# N-CW7_Main.net
KiCad netlist of a schematic drawn in Altium Designer
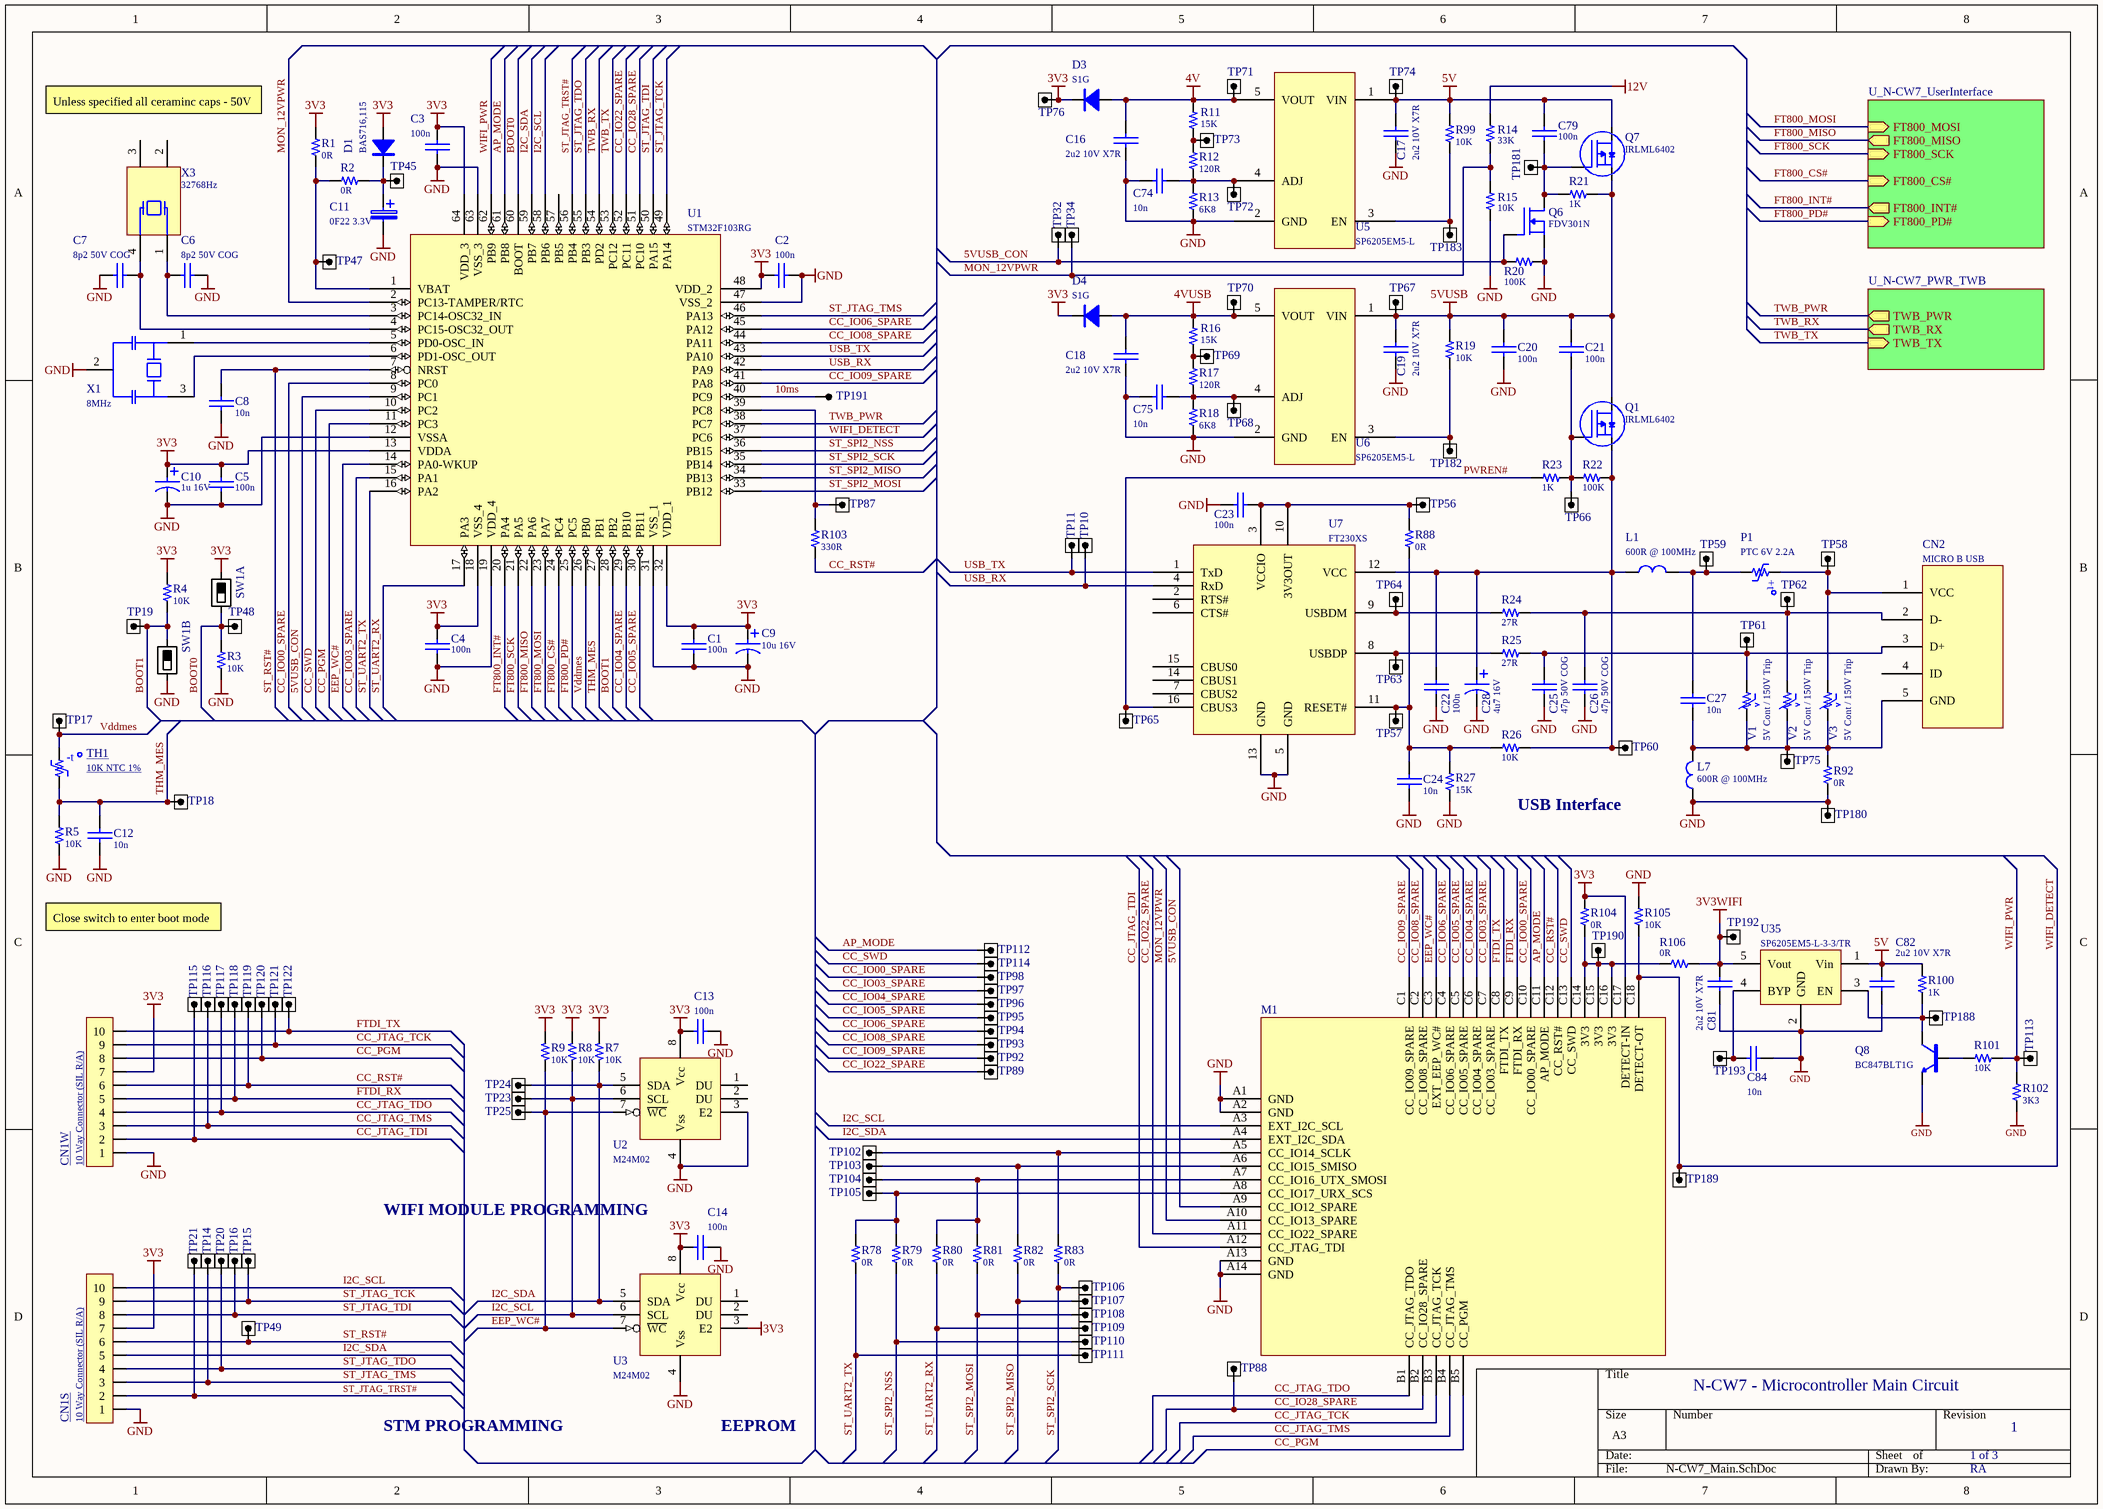
[diagram p0: N-CW7_Main.SchDoc]

(export (version "E")
  (design (tool "Eeschema 10.0.6"))
  (components
    (comp (ref "C1")
      (value "100n")
      (footprint "TDK_0603_T0.80:CAPC1608X08N")
      (description "CAP CER 0.1UF 50V X7R 0603")
      (fields
        (field (name "MANUFACTURER") "TDK")
        (field (name "MANUFACTURER PART NUMBER") "C1608X7R1H104K080AA")
      )
      (libsource (lib "PassiveComponents_Capacitors_Ceramic") (part "TDK_0603_T0.80"))
    )
    (comp (ref "C2")
      (value "100n")
      (footprint "TDK_0603_T0.80:CAPC1608X08N")
      (description "CAP CER 0.1UF 50V X7R 0603")
      (fields
        (field (name "MANUFACTURER") "TDK")
        (field (name "MANUFACTURER PART NUMBER") "C1608X7R1H104K080AA")
      )
      (libsource (lib "PassiveComponents_Capacitors_Ceramic") (part "TDK_0603_T0.80"))
    )
    (comp (ref "C3")
      (value "100n")
      (footprint "TDK_0603_T0.80:CAPC1608X08N")
      (description "CAP CER 0.1UF 50V X7R 0603")
      (fields
        (field (name "MANUFACTURER") "TDK")
        (field (name "MANUFACTURER PART NUMBER") "C1608X7R1H104K080AA")
      )
      (libsource (lib "PassiveComponents_Capacitors_Ceramic") (part "TDK_0603_T0.80"))
    )
    (comp (ref "C4")
      (value "100n")
      (footprint "TDK_0603_T0.80:CAPC1608X08N")
      (description "CAP CER 0.1UF 50V X7R 0603")
      (fields
        (field (name "MANUFACTURER") "TDK")
        (field (name "MANUFACTURER PART NUMBER") "C1608X7R1H104K080AA")
      )
      (libsource (lib "PassiveComponents_Capacitors_Ceramic") (part "TDK_0603_T0.80"))
    )
    (comp (ref "C5")
      (value "100n")
      (footprint "TDK_0603_T0.80:CAPC1608X08N")
      (description "CAP CER 0.1UF 50V X7R 0603")
      (fields
        (field (name "MANUFACTURER") "TDK")
        (field (name "MANUFACTURER PART NUMBER") "C1608X7R1H104K080AA")
      )
      (libsource (lib "PassiveComponents_Capacitors_Ceramic") (part "TDK_0603_T0.80"))
    )
    (comp (ref "C6")
      (value "8p2 50V COG")
      (footprint "KEMET_0603_T0.80:CAPC1608X08N")
      (description "CAP CER 8.2PF 50V C0G/NP0 0603")
      (fields
        (field (name "MANUFACTURER") "KEMET")
        (field (name "MANUFACTURER PART NUMBER") "C0603C829C5GACTU")
      )
      (libsource (lib "PassiveComponents_Capacitors_Ceramic") (part "KEMET_0603_T0.80"))
    )
    (comp (ref "C7")
      (value "8p2 50V COG")
      (footprint "KEMET_0603_T0.80:CAPC1608X08N")
      (description "CAP CER 8.2PF 50V C0G/NP0 0603")
      (fields
        (field (name "MANUFACTURER") "KEMET")
        (field (name "MANUFACTURER PART NUMBER") "C0603C829C5GACTU")
      )
      (libsource (lib "PassiveComponents_Capacitors_Ceramic") (part "KEMET_0603_T0.80"))
    )
    (comp (ref "C8")
      (value "10n")
      (footprint "TDK_0603_T0.80:CAPC1608X08N")
      (description "CAP CER 10000PF 50V X7R 0603")
      (fields
        (field (name "MANUFACTURER") "TDK")
        (field (name "MANUFACTURER PART NUMBER") "C1608X7R1H103K080AA")
      )
      (libsource (lib "PassiveComponents_Capacitors_Ceramic") (part "TDK_0603_T0.80"))
    )
    (comp (ref "C9")
      (value "10u 16V")
      (footprint "KEMET_T494B/3528-21:CAPMP3528X19N")
      (description "CAP TANT 10UF 10% 16V 1411")
      (fields
        (field (name "MANUFACTURER") "KEMET")
        (field (name "MANUFACTURER PART NUMBER") "T494B106K016AT")
      )
      (libsource (lib "PassiveComponents_Capacitors_Tantalum") (part "KEMET_T494B/EIA3528-21"))
    )
    (comp (ref "C10")
      (value "1u 16V")
      (footprint "KEMET_T494A/3216-18:CAPCP3216X16N")
      (description "CAP TANT 1UF 10% 16V 1206")
      (fields
        (field (name "MANUFACTURER") "KEMET")
        (field (name "MANUFACTURER PART NUMBER") "T494A105K016AT")
      )
      (libsource (lib "PassiveComponents_Capacitors_Tantalum") (part "KEMET_T494A/EIA3216-18"))
    )
    (comp (ref "C11")
      (value "0F22 3.3V")
      (footprint "ELNA_RSCSK2243R3D02008U")
      (description "CAP 220MF -20% +80% 3.3V SMD")
      (fields
        (field (name "MANUFACTURER") "Elna")
        (field (name "MANUFACTURER PART NUMBER") "RSCSK2243R3D02008U")
      )
      (libsource (lib "PassiveComponents_Capacitors_Electrolytic") (part "ELNA_RSCSK2243R3D02008U"))
    )
    (comp (ref "C12")
      (value "10n")
      (footprint "TDK_0603_T0.80:CAPC1608X08N")
      (description "CAP CER 10000PF 50V X7R 0603")
      (fields
        (field (name "MANUFACTURER") "TDK")
        (field (name "MANUFACTURER PART NUMBER") "C1608X7R1H103K080AA")
      )
      (libsource (lib "PassiveComponents_Capacitors_Ceramic") (part "TDK_0603_T0.80"))
    )
    (comp (ref "C13")
      (value "100n")
      (footprint "TDK_0603_T0.80:CAPC1608X08N")
      (description "CAP CER 0.1UF 50V X7R 0603")
      (fields
        (field (name "MANUFACTURER") "TDK")
        (field (name "MANUFACTURER PART NUMBER") "C1608X7R1H104K080AA")
      )
      (libsource (lib "PassiveComponents_Capacitors_Ceramic") (part "TDK_0603_T0.80"))
    )
    (comp (ref "C14")
      (value "100n")
      (footprint "TDK_0603_T0.80:CAPC1608X08N")
      (description "CAP CER 0.1UF 50V X7R 0603")
      (fields
        (field (name "MANUFACTURER") "TDK")
        (field (name "MANUFACTURER PART NUMBER") "C1608X7R1H104K080AA")
      )
      (libsource (lib "PassiveComponents_Capacitors_Ceramic") (part "TDK_0603_T0.80"))
    )
    (comp (ref "C16")
      (value "2u2 10V X7R")
      (footprint "TDK_0603_T0.80:CAPC1608X08N")
      (description "CAP CER 2.2UF 10V X7R 0603")
      (fields
        (field (name "MANUFACTURER") "TDK")
        (field (name "MANUFACTURER PART NUMBER") "C1608X7R1A225K080AC")
      )
      (libsource (lib "PassiveComponents_Capacitors_Ceramic") (part "TDK_0603_T0.80"))
    )
    (comp (ref "C17")
      (value "2u2 10V X7R")
      (footprint "TDK_0603_T0.80:CAPC1608X08N")
      (description "CAP CER 2.2UF 10V X7R 0603")
      (fields
        (field (name "MANUFACTURER") "TDK")
        (field (name "MANUFACTURER PART NUMBER") "C1608X7R1A225K080AC")
      )
      (libsource (lib "PassiveComponents_Capacitors_Ceramic") (part "TDK_0603_T0.80"))
    )
    (comp (ref "C18")
      (value "2u2 10V X7R")
      (footprint "TDK_0603_T0.80:CAPC1608X08N")
      (description "CAP CER 2.2UF 10V X7R 0603")
      (fields
        (field (name "MANUFACTURER") "TDK")
        (field (name "MANUFACTURER PART NUMBER") "C1608X7R1A225K080AC")
      )
      (libsource (lib "PassiveComponents_Capacitors_Ceramic") (part "TDK_0603_T0.80"))
    )
    (comp (ref "C19")
      (value "2u2 10V X7R")
      (footprint "TDK_0603_T0.80:CAPC1608X08N")
      (description "CAP CER 2.2UF 10V X7R 0603")
      (fields
        (field (name "MANUFACTURER") "TDK")
        (field (name "MANUFACTURER PART NUMBER") "C1608X7R1A225K080AC")
      )
      (libsource (lib "PassiveComponents_Capacitors_Ceramic") (part "TDK_0603_T0.80"))
    )
    (comp (ref "C20")
      (value "100n")
      (footprint "TDK_0603_T0.80:CAPC1608X08N")
      (description "CAP CER 0.1UF 50V X7R 0603")
      (fields
        (field (name "MANUFACTURER") "TDK")
        (field (name "MANUFACTURER PART NUMBER") "C1608X7R1H104K080AA")
      )
      (libsource (lib "PassiveComponents_Capacitors_Ceramic") (part "TDK_0603_T0.80"))
    )
    (comp (ref "C21")
      (value "100n")
      (footprint "TDK_0603_T0.80:CAPC1608X08N")
      (description "CAP CER 0.1UF 50V X7R 0603")
      (fields
        (field (name "MANUFACTURER") "TDK")
        (field (name "MANUFACTURER PART NUMBER") "C1608X7R1H104K080AA")
      )
      (libsource (lib "PassiveComponents_Capacitors_Ceramic") (part "TDK_0603_T0.80"))
    )
    (comp (ref "C22")
      (value "100n")
      (footprint "TDK_0603_T0.80:CAPC1608X08N")
      (description "CAP CER 0.1UF 50V X7R 0603")
      (fields
        (field (name "MANUFACTURER") "TDK")
        (field (name "MANUFACTURER PART NUMBER") "C1608X7R1H104K080AA")
      )
      (libsource (lib "PassiveComponents_Capacitors_Ceramic") (part "TDK_0603_T0.80"))
    )
    (comp (ref "C23")
      (value "100n")
      (footprint "TDK_0603_T0.80:CAPC1608X08N")
      (description "CAP CER 0.1UF 50V X7R 0603")
      (fields
        (field (name "MANUFACTURER") "TDK")
        (field (name "MANUFACTURER PART NUMBER") "C1608X7R1H104K080AA")
      )
      (libsource (lib "PassiveComponents_Capacitors_Ceramic") (part "TDK_0603_T0.80"))
    )
    (comp (ref "C24")
      (value "10n")
      (footprint "TDK_0603_T0.80:CAPC1608X08N")
      (description "CAP CER 10000PF 50V X7R 0603")
      (fields
        (field (name "MANUFACTURER") "TDK")
        (field (name "MANUFACTURER PART NUMBER") "C1608X7R1H103K080AA")
      )
      (libsource (lib "PassiveComponents_Capacitors_Ceramic") (part "TDK_0603_T0.80"))
    )
    (comp (ref "C25")
      (value "47p 50V COG")
      (footprint "TDK_0603_T0.80:CAPC1608X08N")
      (description "CAP CER 47PF 50V C0G 0603")
      (fields
        (field (name "MANUFACTURER") "TDK")
        (field (name "MANUFACTURER PART NUMBER") "C1608C0G1H470J080AA")
      )
      (libsource (lib "PassiveComponents_Capacitors_Ceramic") (part "TDK_0603_T0.80"))
    )
    (comp (ref "C26")
      (value "47p 50V COG")
      (footprint "TDK_0603_T0.80:CAPC1608X08N")
      (description "CAP CER 47PF 50V C0G 0603")
      (fields
        (field (name "MANUFACTURER") "TDK")
        (field (name "MANUFACTURER PART NUMBER") "C1608C0G1H470J080AA")
      )
      (libsource (lib "PassiveComponents_Capacitors_Ceramic") (part "TDK_0603_T0.80"))
    )
    (comp (ref "C27")
      (value "10n")
      (footprint "TDK_0603_T0.80:CAPC1608X08N")
      (description "CAP CER 10000PF 50V X7R 0603")
      (fields
        (field (name "MANUFACTURER") "TDK")
        (field (name "MANUFACTURER PART NUMBER") "C1608X7R1H103K080AA")
      )
      (libsource (lib "PassiveComponents_Capacitors_Ceramic") (part "TDK_0603_T0.80"))
    )
    (comp (ref "C28")
      (value "4u7 16V")
      (footprint "KEMET_T494A/3216-18:CAPCP3216X16N")
      (description "CAP TANT 4.7UF 10% 16V 1206")
      (fields
        (field (name "MANUFACTURER") "KEMET")
        (field (name "MANUFACTURER PART NUMBER") "T494A475K016AT")
      )
      (libsource (lib "PassiveComponents_Capacitors_Tantalum") (part "KEMET_T494A/EIA3216-18"))
    )
    (comp (ref "C74")
      (value "10n")
      (footprint "TDK_0603_T0.80:CAPC1608X08N")
      (description "CAP CER 10000PF 50V X7R 0603")
      (fields
        (field (name "MANUFACTURER") "TDK")
        (field (name "MANUFACTURER PART NUMBER") "C1608X7R1H103K080AA")
      )
      (libsource (lib "PassiveComponents_Capacitors_Ceramic") (part "TDK_0603_T0.80"))
    )
    (comp (ref "C75")
      (value "10n")
      (footprint "TDK_0603_T0.80:CAPC1608X08N")
      (description "CAP CER 10000PF 50V X7R 0603")
      (fields
        (field (name "MANUFACTURER") "TDK")
        (field (name "MANUFACTURER PART NUMBER") "C1608X7R1H103K080AA")
      )
      (libsource (lib "PassiveComponents_Capacitors_Ceramic") (part "TDK_0603_T0.80"))
    )
    (comp (ref "C79")
      (value "100n")
      (footprint "TDK_0603_T0.80:CAPC1608X08N")
      (description "CAP CER 0.1UF 50V X7R 0603")
      (fields
        (field (name "MANUFACTURER") "TDK")
        (field (name "MANUFACTURER PART NUMBER") "C1608X7R1H104K080AA")
      )
      (libsource (lib "PassiveComponents_Capacitors_Ceramic") (part "TDK_0603_T0.80"))
    )
    (comp (ref "C81")
      (value "2u2 10V X7R")
      (footprint "TDK_0603_T0.80:CAPC1608X08N")
      (description "CAP CER 2.2UF 10V X7R 0603")
      (fields
        (field (name "MANUFACTURER") "TDK")
        (field (name "MANUFACTURER PART NUMBER") "C1608X7R1A225K080AC")
      )
      (libsource (lib "PassiveComponents_Capacitors_Ceramic") (part "TDK_0603_T0.80"))
    )
    (comp (ref "C82")
      (value "2u2 10V X7R")
      (footprint "TDK_0603_T0.80:CAPC1608X08N")
      (description "CAP CER 2.2UF 10V X7R 0603")
      (fields
        (field (name "MANUFACTURER") "TDK")
        (field (name "MANUFACTURER PART NUMBER") "C1608X7R1A225K080AC")
      )
      (libsource (lib "PassiveComponents_Capacitors_Ceramic") (part "TDK_0603_T0.80"))
    )
    (comp (ref "C84")
      (value "10n")
      (footprint "TDK_0603_T0.80:CAPC1608X08N")
      (description "CAP CER 10000PF 50V X7R 0603")
      (fields
        (field (name "MANUFACTURER") "TDK")
        (field (name "MANUFACTURER PART NUMBER") "C1608X7R1H103K080AA")
      )
      (libsource (lib "PassiveComponents_Capacitors_Ceramic") (part "TDK_0603_T0.80"))
    )
    (comp (ref "CN1S")
      (value "10 Way Connector (SIL R/A)")
      (footprint "SULLINS_PPTC101LGBN-RC")
      (description "CONN HDR 10POS 0.1 TIN PCB R/A")
      (fields
        (field (name "MANUFACTURER") "Sullins")
        (field (name "MANUFACTURER PART NUMBER") "PPTC101LGBN-RC")
      )
      (libsource (lib "Connectors") (part "SULLINS_10W_SIL_HDR_RA_2.54MM"))
    )
    (comp (ref "CN1W")
      (value "10 Way Connector (SIL R/A)")
      (footprint "SULLINS_PPTC101LGBN-RC")
      (description "CONN HDR 10POS 0.1 TIN PCB R/A")
      (fields
        (field (name "MANUFACTURER") "Sullins")
        (field (name "MANUFACTURER PART NUMBER") "PPTC101LGBN-RC")
      )
      (libsource (lib "Connectors") (part "SULLINS_10W_SIL_HDR_RA_2.54MM"))
    )
    (comp (ref "CN2")
      (value "MICRO B USB")
      (footprint "MOLEX:47346-1001")
      (description "CONN RCPT USB2.0 MICRO B SMD R/A")
      (fields (field (name "MANUFACTURER") "Molex") (field (name "MANUFACTURER PART NUMBER") "47346-1001"))
      (libsource (lib "Connectors") (part "MOLEX_USB_MICRO_B_SMD_RA"))
    )
    (comp (ref "D1")
      (value "BAS716,115")
      (footprint "NEXPERIA_BAS716,115_SOD523:SODFL160X65-2N")
      (description "DIODE STANDARD 75V 200MA SOD523")
      (fields (field (name "MANUFACTURER") "Nexperia") (field (name "MANUFACTURER PART NUMBER") "BAS716115"))
      (libsource (lib "DiscreteSemiconductors_Diodes_Rectifier") (part "NEXPERIA_BAS716,115_SOD523"))
    )
    (comp (ref "D3")
      (value "S1G")
      (footprint "DIODESINC_S1G_SMA_D0214AC:DIOM4326X24N")
      (description "DIODE GEN PURP 400V 1A SMA")
      (fields (field (name "MANUFACTURER") "Diodes") (field (name "MANUFACTURER PART NUMBER") "S1G-13-F"))
      (libsource (lib "DiscreteSemiconductors_Diodes_Rectifier") (part "DIODESINC_S1G_SMA_D0214AC"))
    )
    (comp (ref "D4")
      (value "S1G")
      (footprint "DIODESINC_S1G_SMA_D0214AC:DIOM4326X24N")
      (description "DIODE GEN PURP 400V 1A SMA")
      (fields (field (name "MANUFACTURER") "Diodes") (field (name "MANUFACTURER PART NUMBER") "S1G-13-F"))
      (libsource (lib "DiscreteSemiconductors_Diodes_Rectifier") (part "DIODESINC_S1G_SMA_D0214AC"))
    )
    (comp (ref "L1")
      (value "600R @ 100MHz")
      (footprint "LAIRD_MI0805K601R-10:INDC2012X09N")
      (description "FERRITE BEAD 600 OHM 0805 1LN")
      (fields
        (field (name "MANUFACTURER") "Laird")
        (field (name "MANUFACTURER PART NUMBER") "MI0805K601R-10")
      )
      (libsource (lib "PassiveComponents_Inductors") (part "LAIRD_MI0805K601R-10"))
    )
    (comp (ref "L7")
      (value "600R @ 100MHz")
      (footprint "LAIRD_MI0805K601R-10:INDC2012X09N")
      (description "FERRITE BEAD 600 OHM 0805 1LN")
      (fields
        (field (name "MANUFACTURER") "Laird")
        (field (name "MANUFACTURER PART NUMBER") "MI0805K601R-10")
      )
      (libsource (lib "PassiveComponents_Inductors") (part "LAIRD_MI0805K601R-10"))
    )
    (comp (ref "M1")
      (value "MB-WIFI-CC3200Rev01")
      (footprint "MB-WIFI-CC3200Rev01")
      (description "Module - Wi-Fi Module (CC3200)")
      (libsource (lib "CustomModules") (part "MB-WIFI-CC3200Rev01"))
    )
    (comp (ref "P1")
      (value "PTC 6V 2.2A")
      (footprint "BOURNS_MF-MSMF110-2:INDC4632X08N")
      (description "PTC RESET FUSE 24V 1.1A 1812")
      (fields
        (field (name "MANUFACTURER") "Bourns")
        (field (name "MANUFACTURER PART NUMBER") "MF-MSMF110/24X-2")
      )
      (libsource (lib "CircuitProtection_Fuses") (part "BOURNS_MF-MSMF110-2"))
    )
    (comp (ref "Q1")
      (value "IRLML6402")
      (footprint "IR_IRLML6402TRPBF_SOT23:SOT95P237X112-3N")
      (description "MOSFET P-CH 20V 3.7A SOT23")
      (fields
        (field (name "MANUFACTURER") "Infineon")
        (field (name "MANUFACTURER PART NUMBER") "IRLML6402TRPBF")
      )
      (libsource (lib "DiscreteSemiconductors_Transistors_JFETs") (part "IR_IRLML6402TRPBF_SOT23"))
    )
    (comp (ref "Q6")
      (value "FDV301N")
      (footprint "ONSEMI_FDV301N_SOT23:SOT95P230X110-3N")
      (description "MOSFET N-CH 25V 220MA SOT23")
      (fields (field (name "MANUFACTURER") "ON Semiconductor / Fairchild"))
      (libsource (lib "DiscreteSemiconductors_Transistors_JFETs") (part "ONSEMI_FDV301N_SOT23"))
    )
    (comp (ref "Q7")
      (value "IRLML6402")
      (footprint "IR_IRLML6402TRPBF_SOT23:SOT95P237X112-3N")
      (description "MOSFET P-CH 20V 3.7A SOT23")
      (fields
        (field (name "MANUFACTURER") "Infineon")
        (field (name "MANUFACTURER PART NUMBER") "IRLML6402TRPBF")
      )
      (libsource (lib "DiscreteSemiconductors_Transistors_JFETs") (part "IR_IRLML6402TRPBF_SOT23"))
    )
    (comp (ref "Q8")
      (value "BC847BLT1G")
      (footprint "ONSEMI_BC847BLT1G_SOT23:SOT95P230X110-3N")
      (description "TRANS NPN 45V 100MA SOT23-3")
      (fields (field (name "MANUFACTURER") "ON Semiconductor"))
      (libsource (lib "DiscreteSemiconductors_Transistors_BJTs") (part "ONSEMI_BC847BLT1G_SOT23"))
    )
    (comp (ref "R1")
      (value "0R")
      (footprint "YAGEO_0603_T0.55:RESC1608X06N")
      (description "RES 0 OHM JUMPER 1/10W 0603")
      (fields
        (field (name "MANUFACTURER") "Yageo")
        (field (name "MANUFACTURER PART NUMBER") "RC0603FR-070RL")
      )
      (libsource (lib "PassiveComponents_Resistors_ChipSMD") (part "YAGEO_0603_T0.55"))
    )
    (comp (ref "R2")
      (value "0R")
      (footprint "YAGEO_0603_T0.55:RESC1608X06N")
      (description "RES 0 OHM JUMPER 1/10W 0603")
      (fields
        (field (name "MANUFACTURER") "Yageo")
        (field (name "MANUFACTURER PART NUMBER") "RC0603FR-070RL")
      )
      (libsource (lib "PassiveComponents_Resistors_ChipSMD") (part "YAGEO_0603_T0.55"))
    )
    (comp (ref "R3")
      (value "10K")
      (footprint "YAGEO_0603_T0.55:RESC1608X06N")
      (description "RES 10K OHM 1% 1/10W 0603")
      (fields
        (field (name "MANUFACTURER") "Yageo")
        (field (name "MANUFACTURER PART NUMBER") "RC0603FR-0710KL")
      )
      (libsource (lib "PassiveComponents_Resistors_ChipSMD") (part "YAGEO_0603_T0.55"))
    )
    (comp (ref "R4")
      (value "10K")
      (footprint "YAGEO_0603_T0.55:RESC1608X06N")
      (description "RES 10K OHM 1% 1/10W 0603")
      (fields
        (field (name "MANUFACTURER") "Yageo")
        (field (name "MANUFACTURER PART NUMBER") "RC0603FR-0710KL")
      )
      (libsource (lib "PassiveComponents_Resistors_ChipSMD") (part "YAGEO_0603_T0.55"))
    )
    (comp (ref "R5")
      (value "10K")
      (footprint "YAGEO_0603_T0.55:RESC1608X06N")
      (description "RES 10K OHM 1% 1/10W 0603")
      (fields
        (field (name "MANUFACTURER") "Yageo")
        (field (name "MANUFACTURER PART NUMBER") "RC0603FR-0710KL")
      )
      (libsource (lib "PassiveComponents_Resistors_ChipSMD") (part "YAGEO_0603_T0.55"))
    )
    (comp (ref "R7")
      (value "10K")
      (footprint "YAGEO_0603_T0.55:RESC1608X06N")
      (description "RES 10K OHM 1% 1/10W 0603")
      (fields
        (field (name "MANUFACTURER") "Yageo")
        (field (name "MANUFACTURER PART NUMBER") "RC0603FR-0710KL")
      )
      (libsource (lib "PassiveComponents_Resistors_ChipSMD") (part "YAGEO_0603_T0.55"))
    )
    (comp (ref "R8")
      (value "10K")
      (footprint "YAGEO_0603_T0.55:RESC1608X06N")
      (description "RES 10K OHM 1% 1/10W 0603")
      (fields
        (field (name "MANUFACTURER") "Yageo")
        (field (name "MANUFACTURER PART NUMBER") "RC0603FR-0710KL")
      )
      (libsource (lib "PassiveComponents_Resistors_ChipSMD") (part "YAGEO_0603_T0.55"))
    )
    (comp (ref "R9")
      (value "10K")
      (footprint "YAGEO_0603_T0.55:RESC1608X06N")
      (description "RES 10K OHM 1% 1/10W 0603")
      (fields
        (field (name "MANUFACTURER") "Yageo")
        (field (name "MANUFACTURER PART NUMBER") "RC0603FR-0710KL")
      )
      (libsource (lib "PassiveComponents_Resistors_ChipSMD") (part "YAGEO_0603_T0.55"))
    )
    (comp (ref "R11")
      (value "15K")
      (footprint "YAGEO_0603_T0.55:RESC1608X06N")
      (description "RES 15K OHM 1% 1/10W 0603")
      (fields
        (field (name "MANUFACTURER") "Yageo")
        (field (name "MANUFACTURER PART NUMBER") "RC0603FR-0715KL")
      )
      (libsource (lib "PassiveComponents_Resistors_ChipSMD") (part "YAGEO_0603_T0.55"))
    )
    (comp (ref "R12")
      (value "120R")
      (footprint "YAGEO_0603_T0.55:RESC1608X06N")
      (description "RES 120 OHM 1% 1/10W 0603")
      (fields
        (field (name "MANUFACTURER") "Yageo")
        (field (name "MANUFACTURER PART NUMBER") "RC0603FR-07120RL")
      )
      (libsource (lib "PassiveComponents_Resistors_ChipSMD") (part "YAGEO_0603_T0.55"))
    )
    (comp (ref "R13")
      (value "6K8")
      (footprint "YAGEO_0603_T0.55:RESC1608X06N")
      (description "RES 6.8K OHM 1% 1/10W 0603")
      (fields
        (field (name "MANUFACTURER") "Yageo")
        (field (name "MANUFACTURER PART NUMBER") "RC0603FR-076K8L")
      )
      (libsource (lib "PassiveComponents_Resistors_ChipSMD") (part "YAGEO_0603_T0.55"))
    )
    (comp (ref "R14")
      (value "33K")
      (footprint "YAGEO_0603_T0.55:RESC1608X06N")
      (description "RES 33K OHM 1% 1/10W 0603")
      (fields
        (field (name "MANUFACTURER") "Yageo")
        (field (name "MANUFACTURER PART NUMBER") "RC0603FR-0733KL")
      )
      (libsource (lib "PassiveComponents_Resistors_ChipSMD") (part "YAGEO_0603_T0.55"))
    )
    (comp (ref "R15")
      (value "10K")
      (footprint "YAGEO_0603_T0.55:RESC1608X06N")
      (description "RES 10K OHM 1% 1/10W 0603")
      (fields
        (field (name "MANUFACTURER") "Yageo")
        (field (name "MANUFACTURER PART NUMBER") "RC0603FR-0710KL")
      )
      (libsource (lib "PassiveComponents_Resistors_ChipSMD") (part "YAGEO_0603_T0.55"))
    )
    (comp (ref "R16")
      (value "15K")
      (footprint "YAGEO_0603_T0.55:RESC1608X06N")
      (description "RES 15K OHM 1% 1/10W 0603")
      (fields
        (field (name "MANUFACTURER") "Yageo")
        (field (name "MANUFACTURER PART NUMBER") "RC0603FR-0715KL")
      )
      (libsource (lib "PassiveComponents_Resistors_ChipSMD") (part "YAGEO_0603_T0.55"))
    )
    (comp (ref "R17")
      (value "120R")
      (footprint "YAGEO_0603_T0.55:RESC1608X06N")
      (description "RES 120 OHM 1% 1/10W 0603")
      (fields
        (field (name "MANUFACTURER") "Yageo")
        (field (name "MANUFACTURER PART NUMBER") "RC0603FR-07120RL")
      )
      (libsource (lib "PassiveComponents_Resistors_ChipSMD") (part "YAGEO_0603_T0.55"))
    )
    (comp (ref "R18")
      (value "6K8")
      (footprint "YAGEO_0603_T0.55:RESC1608X06N")
      (description "RES 6.8K OHM 1% 1/10W 0603")
      (fields
        (field (name "MANUFACTURER") "Yageo")
        (field (name "MANUFACTURER PART NUMBER") "RC0603FR-076K8L")
      )
      (libsource (lib "PassiveComponents_Resistors_ChipSMD") (part "YAGEO_0603_T0.55"))
    )
    (comp (ref "R19")
      (value "10K")
      (footprint "YAGEO_0603_T0.55:RESC1608X06N")
      (description "RES 10K OHM 1% 1/10W 0603")
      (fields
        (field (name "MANUFACTURER") "Yageo")
        (field (name "MANUFACTURER PART NUMBER") "RC0603FR-0710KL")
      )
      (libsource (lib "PassiveComponents_Resistors_ChipSMD") (part "YAGEO_0603_T0.55"))
    )
    (comp (ref "R20")
      (value "100K")
      (footprint "YAGEO_0603_T0.55:RESC1608X06N")
      (description "RES 100K OHM 1% 1/10W 0603")
      (fields
        (field (name "MANUFACTURER") "Yageo")
        (field (name "MANUFACTURER PART NUMBER") "RC0603FR-07100KL")
      )
      (libsource (lib "PassiveComponents_Resistors_ChipSMD") (part "YAGEO_0603_T0.55"))
    )
    (comp (ref "R21")
      (value "1K")
      (footprint "YAGEO_0603_T0.55:RESC1608X06N")
      (description "RES 1K OHM 1% 1/10W 0603")
      (fields
        (field (name "MANUFACTURER") "Yageo")
        (field (name "MANUFACTURER PART NUMBER") "RC0603FR-071KL")
      )
      (libsource (lib "PassiveComponents_Resistors_ChipSMD") (part "YAGEO_0603_T0.55"))
    )
    (comp (ref "R22")
      (value "100K")
      (footprint "YAGEO_0603_T0.55:RESC1608X06N")
      (description "RES 100K OHM 1% 1/10W 0603")
      (fields
        (field (name "MANUFACTURER") "Yageo")
        (field (name "MANUFACTURER PART NUMBER") "RC0603FR-07100KL")
      )
      (libsource (lib "PassiveComponents_Resistors_ChipSMD") (part "YAGEO_0603_T0.55"))
    )
    (comp (ref "R23")
      (value "1K")
      (footprint "YAGEO_0603_T0.55:RESC1608X06N")
      (description "RES 1K OHM 1% 1/10W 0603")
      (fields
        (field (name "MANUFACTURER") "Yageo")
        (field (name "MANUFACTURER PART NUMBER") "RC0603FR-071KL")
      )
      (libsource (lib "PassiveComponents_Resistors_ChipSMD") (part "YAGEO_0603_T0.55"))
    )
    (comp (ref "R24")
      (value "27R")
      (footprint "YAGEO_0603_T0.55:RESC1608X06N")
      (description "RES 27 OHM 1% 1/10W 0603")
      (fields
        (field (name "MANUFACTURER") "Yageo")
        (field (name "MANUFACTURER PART NUMBER") "RC0603FR-0727RL")
      )
      (libsource (lib "PassiveComponents_Resistors_ChipSMD") (part "YAGEO_0603_T0.55"))
    )
    (comp (ref "R25")
      (value "27R")
      (footprint "YAGEO_0603_T0.55:RESC1608X06N")
      (description "RES 27 OHM 1% 1/10W 0603")
      (fields
        (field (name "MANUFACTURER") "Yageo")
        (field (name "MANUFACTURER PART NUMBER") "RC0603FR-0727RL")
      )
      (libsource (lib "PassiveComponents_Resistors_ChipSMD") (part "YAGEO_0603_T0.55"))
    )
    (comp (ref "R26")
      (value "10K")
      (footprint "YAGEO_0603_T0.55:RESC1608X06N")
      (description "RES 10K OHM 1% 1/10W 0603")
      (fields
        (field (name "MANUFACTURER") "Yageo")
        (field (name "MANUFACTURER PART NUMBER") "RC0603FR-0710KL")
      )
      (libsource (lib "PassiveComponents_Resistors_ChipSMD") (part "YAGEO_0603_T0.55"))
    )
    (comp (ref "R27")
      (value "15K")
      (footprint "YAGEO_0603_T0.55:RESC1608X06N")
      (description "RES 15K OHM 1% 1/10W 0603")
      (fields
        (field (name "MANUFACTURER") "Yageo")
        (field (name "MANUFACTURER PART NUMBER") "RC0603FR-0715KL")
      )
      (libsource (lib "PassiveComponents_Resistors_ChipSMD") (part "YAGEO_0603_T0.55"))
    )
    (comp (ref "R78")
      (value "0R")
      (footprint "YAGEO_0603_T0.55:RESC1608X06N")
      (description "RES 0 OHM JUMPER 1/10W 0603")
      (fields
        (field (name "MANUFACTURER") "Yageo")
        (field (name "MANUFACTURER PART NUMBER") "RC0603FR-070RL")
      )
      (libsource (lib "PassiveComponents_Resistors_ChipSMD") (part "YAGEO_0603_T0.55"))
    )
    (comp (ref "R79")
      (value "0R")
      (footprint "YAGEO_0603_T0.55:RESC1608X06N")
      (description "RES 0 OHM JUMPER 1/10W 0603")
      (fields
        (field (name "MANUFACTURER") "Yageo")
        (field (name "MANUFACTURER PART NUMBER") "RC0603FR-070RL")
      )
      (libsource (lib "PassiveComponents_Resistors_ChipSMD") (part "YAGEO_0603_T0.55"))
    )
    (comp (ref "R80")
      (value "0R")
      (footprint "YAGEO_0603_T0.55:RESC1608X06N")
      (description "RES 0 OHM JUMPER 1/10W 0603")
      (fields
        (field (name "MANUFACTURER") "Yageo")
        (field (name "MANUFACTURER PART NUMBER") "RC0603FR-070RL")
      )
      (libsource (lib "PassiveComponents_Resistors_ChipSMD") (part "YAGEO_0603_T0.55"))
    )
    (comp (ref "R81")
      (value "0R")
      (footprint "YAGEO_0603_T0.55:RESC1608X06N")
      (description "RES 0 OHM JUMPER 1/10W 0603")
      (fields
        (field (name "MANUFACTURER") "Yageo")
        (field (name "MANUFACTURER PART NUMBER") "RC0603FR-070RL")
      )
      (libsource (lib "PassiveComponents_Resistors_ChipSMD") (part "YAGEO_0603_T0.55"))
    )
    (comp (ref "R82")
      (value "0R")
      (footprint "YAGEO_0603_T0.55:RESC1608X06N")
      (description "RES 0 OHM JUMPER 1/10W 0603")
      (fields
        (field (name "MANUFACTURER") "Yageo")
        (field (name "MANUFACTURER PART NUMBER") "RC0603FR-070RL")
      )
      (libsource (lib "PassiveComponents_Resistors_ChipSMD") (part "YAGEO_0603_T0.55"))
    )
    (comp (ref "R83")
      (value "0R")
      (footprint "YAGEO_0603_T0.55:RESC1608X06N")
      (description "RES 0 OHM JUMPER 1/10W 0603")
      (fields
        (field (name "MANUFACTURER") "Yageo")
        (field (name "MANUFACTURER PART NUMBER") "RC0603FR-070RL")
      )
      (libsource (lib "PassiveComponents_Resistors_ChipSMD") (part "YAGEO_0603_T0.55"))
    )
    (comp (ref "R88")
      (value "0R")
      (footprint "YAGEO_0603_T0.55:RESC1608X06N")
      (description "RES 0 OHM JUMPER 1/10W 0603")
      (fields
        (field (name "MANUFACTURER") "Yageo")
        (field (name "MANUFACTURER PART NUMBER") "RC0603FR-070RL")
      )
      (libsource (lib "PassiveComponents_Resistors_ChipSMD") (part "YAGEO_0603_T0.55"))
    )
    (comp (ref "R92")
      (value "0R")
      (footprint "YAGEO_0603_T0.55:RESC1608X06N")
      (description "RES 0 OHM JUMPER 1/10W 0603")
      (fields
        (field (name "MANUFACTURER") "Yageo")
        (field (name "MANUFACTURER PART NUMBER") "RC0603FR-070RL")
      )
      (libsource (lib "PassiveComponents_Resistors_ChipSMD") (part "YAGEO_0603_T0.55"))
    )
    (comp (ref "R99")
      (value "10K")
      (footprint "YAGEO_0603_T0.55:RESC1608X06N")
      (description "RES 10K OHM 1% 1/10W 0603")
      (fields
        (field (name "MANUFACTURER") "Yageo")
        (field (name "MANUFACTURER PART NUMBER") "RC0603FR-0710KL")
      )
      (libsource (lib "PassiveComponents_Resistors_ChipSMD") (part "YAGEO_0603_T0.55"))
    )
    (comp (ref "R100")
      (value "1K")
      (footprint "YAGEO_0603_T0.55:RESC1608X06N")
      (description "RES 1K OHM 1% 1/10W 0603")
      (fields
        (field (name "MANUFACTURER") "Yageo")
        (field (name "MANUFACTURER PART NUMBER") "RC0603FR-071KL")
      )
      (libsource (lib "PassiveComponents_Resistors_ChipSMD") (part "YAGEO_0603_T0.55"))
    )
    (comp (ref "R101")
      (value "10K")
      (footprint "YAGEO_0603_T0.55:RESC1608X06N")
      (description "RES 10K OHM 1% 1/10W 0603")
      (fields
        (field (name "MANUFACTURER") "Yageo")
        (field (name "MANUFACTURER PART NUMBER") "RC0603FR-0710KL")
      )
      (libsource (lib "PassiveComponents_Resistors_ChipSMD") (part "YAGEO_0603_T0.55"))
    )
    (comp (ref "R102")
      (value "3K3")
      (footprint "YAGEO_0603_T0.55:RESC1608X06N")
      (description "RES 3.3K OHM 1% 1/10W 0603")
      (fields
        (field (name "MANUFACTURER") "Yageo")
        (field (name "MANUFACTURER PART NUMBER") "RC0603FR-073K3L")
      )
      (libsource (lib "PassiveComponents_Resistors_ChipSMD") (part "YAGEO_0603_T0.55"))
    )
    (comp (ref "R103")
      (value "330R")
      (footprint "YAGEO_0603_T0.55:RESC1608X06N")
      (description "RES 330 OHM 1% 1/10W 0603")
      (fields
        (field (name "MANUFACTURER") "Yageo")
        (field (name "MANUFACTURER PART NUMBER") "RC0603FR-07330RL")
      )
      (libsource (lib "PassiveComponents_Resistors_ChipSMD") (part "YAGEO_0603_T0.55"))
    )
    (comp (ref "R104")
      (value "0R")
      (footprint "YAGEO_0603_T0.55:RESC1608X06N")
      (description "RES 0 OHM JUMPER 1/10W 0603")
      (fields
        (field (name "MANUFACTURER") "Yageo")
        (field (name "MANUFACTURER PART NUMBER") "RC0603FR-070RL")
      )
      (libsource (lib "PassiveComponents_Resistors_ChipSMD") (part "YAGEO_0603_T0.55"))
    )
    (comp (ref "R105")
      (value "10K")
      (footprint "YAGEO_0603_T0.55:RESC1608X06N")
      (description "RES 10K OHM 1% 1/10W 0603")
      (fields
        (field (name "MANUFACTURER") "Yageo")
        (field (name "MANUFACTURER PART NUMBER") "RC0603FR-0710KL")
      )
      (libsource (lib "PassiveComponents_Resistors_ChipSMD") (part "YAGEO_0603_T0.55"))
    )
    (comp (ref "R106")
      (value "0R")
      (footprint "YAGEO_0603_T0.55:RESC1608X06N")
      (description "RES 0 OHM JUMPER 1/10W 0603")
      (fields
        (field (name "MANUFACTURER") "Yageo")
        (field (name "MANUFACTURER PART NUMBER") "RC0603FR-070RL")
      )
      (libsource (lib "PassiveComponents_Resistors_ChipSMD") (part "YAGEO_0603_T0.55"))
    )
    (comp (ref "SW1A")
      (value "SPST")
      (footprint "COPAL_CHS-02B")
      (description "SWITCH SLIDE DIP SPST 0.1A 6V")
      (fields (field (name "MANUFACTURER") "Nidec Copal") (field (name "MANUFACTURER PART NUMBER") "CHS-02B"))
      (libsource (lib "PassiveComponents_Switches") (part "COPAL_CHS-02B"))
    )
    (comp (ref "SW1B")
      (value "SPST")
      (footprint "COPAL_CHS-02B")
      (description "SWITCH SLIDE DIP SPST 0.1A 6V")
      (fields (field (name "MANUFACTURER") "Nidec Copal") (field (name "MANUFACTURER PART NUMBER") "CHS-02B"))
      (libsource (lib "PassiveComponents_Switches") (part "COPAL_CHS-02B"))
    )
    (comp (ref "TH1")
      (value "10K NTC 1%")
      (footprint "NETWORKER_THERMISTOR_2.54MM")
      (description "THER 10K 1% LEAD MMC SC25 (450103-006AQ)")
      (libsource (lib "CustomParts") (part "NETWORKER_THERMISTOR"))
    )
    (comp (ref "TP10")
      (value "TESTPOINT_OCTAGONAL")
      (footprint "TESTPOINT_OCTAGONAL")
      (libsource (lib "Miscellaneous") (part "TESTPOINT_OCTAGONAL"))
    )
    (comp (ref "TP11")
      (value "TESTPOINT_OCTAGONAL")
      (footprint "TESTPOINT_OCTAGONAL")
      (libsource (lib "Miscellaneous") (part "TESTPOINT_OCTAGONAL"))
    )
    (comp (ref "TP14")
      (value "TESTPOINT_OCTAGONAL")
      (footprint "TESTPOINT_OCTAGONAL")
      (libsource (lib "Miscellaneous") (part "TESTPOINT_OCTAGONAL"))
    )
    (comp (ref "TP15")
      (value "TESTPOINT_OCTAGONAL")
      (footprint "TESTPOINT_OCTAGONAL")
      (libsource (lib "Miscellaneous") (part "TESTPOINT_OCTAGONAL"))
    )
    (comp (ref "TP16")
      (value "TESTPOINT_OCTAGONAL")
      (footprint "TESTPOINT_OCTAGONAL")
      (libsource (lib "Miscellaneous") (part "TESTPOINT_OCTAGONAL"))
    )
    (comp (ref "TP17")
      (value "TESTPOINT_OCTAGONAL")
      (footprint "TESTPOINT_OCTAGONAL")
      (libsource (lib "Miscellaneous") (part "TESTPOINT_OCTAGONAL"))
    )
    (comp (ref "TP18")
      (value "TESTPOINT_OCTAGONAL")
      (footprint "TESTPOINT_OCTAGONAL")
      (libsource (lib "") (part "TESTPOINT_OCTAGONAL_2"))
    )
    (comp (ref "TP19")
      (value "TESTPOINT_OCTAGONAL")
      (footprint "TESTPOINT_OCTAGONAL")
      (libsource (lib "") (part "TESTPOINT_OCTAGONAL_3"))
    )
    (comp (ref "TP20")
      (value "TESTPOINT_OCTAGONAL")
      (footprint "TESTPOINT_OCTAGONAL")
      (libsource (lib "Miscellaneous") (part "TESTPOINT_OCTAGONAL"))
    )
    (comp (ref "TP21")
      (value "TESTPOINT_OCTAGONAL")
      (footprint "TESTPOINT_OCTAGONAL")
      (libsource (lib "Miscellaneous") (part "TESTPOINT_OCTAGONAL"))
    )
    (comp (ref "TP23")
      (value "TESTPOINT_OCTAGONAL")
      (footprint "TESTPOINT_OCTAGONAL")
      (libsource (lib "") (part "TESTPOINT_OCTAGONAL_3"))
    )
    (comp (ref "TP24")
      (value "TESTPOINT_OCTAGONAL")
      (footprint "TESTPOINT_OCTAGONAL")
      (libsource (lib "") (part "TESTPOINT_OCTAGONAL_3"))
    )
    (comp (ref "TP25")
      (value "TESTPOINT_OCTAGONAL")
      (footprint "TESTPOINT_OCTAGONAL")
      (libsource (lib "") (part "TESTPOINT_OCTAGONAL_3"))
    )
    (comp (ref "TP32")
      (value "TESTPOINT_OCTAGONAL")
      (footprint "TESTPOINT_OCTAGONAL")
      (libsource (lib "Miscellaneous") (part "TESTPOINT_OCTAGONAL"))
    )
    (comp (ref "TP34")
      (value "TESTPOINT_OCTAGONAL")
      (footprint "TESTPOINT_OCTAGONAL")
      (libsource (lib "Miscellaneous") (part "TESTPOINT_OCTAGONAL"))
    )
    (comp (ref "TP45")
      (value "TESTPOINT_OCTAGONAL")
      (footprint "TESTPOINT_OCTAGONAL")
      (libsource (lib "") (part "TESTPOINT_OCTAGONAL_2"))
    )
    (comp (ref "TP47")
      (value "TESTPOINT_OCTAGONAL")
      (footprint "TESTPOINT_OCTAGONAL")
      (libsource (lib "") (part "TESTPOINT_OCTAGONAL_2"))
    )
    (comp (ref "TP48")
      (value "TESTPOINT_OCTAGONAL")
      (footprint "TESTPOINT_OCTAGONAL")
      (libsource (lib "") (part "TESTPOINT_OCTAGONAL_2"))
    )
    (comp (ref "TP49")
      (value "TESTPOINT_OCTAGONAL")
      (footprint "TESTPOINT_OCTAGONAL")
      (libsource (lib "Miscellaneous") (part "TESTPOINT_OCTAGONAL"))
    )
    (comp (ref "TP56")
      (value "TESTPOINT_OCTAGONAL")
      (footprint "TESTPOINT_OCTAGONAL")
      (libsource (lib "") (part "TESTPOINT_OCTAGONAL_2"))
    )
    (comp (ref "TP57")
      (value "TESTPOINT_OCTAGONAL")
      (footprint "TESTPOINT_OCTAGONAL")
      (libsource (lib "") (part "TESTPOINT_OCTAGONAL_1"))
    )
    (comp (ref "TP58")
      (value "TESTPOINT_OCTAGONAL")
      (footprint "TESTPOINT_OCTAGONAL")
      (libsource (lib "Miscellaneous") (part "TESTPOINT_OCTAGONAL"))
    )
    (comp (ref "TP59")
      (value "TESTPOINT_OCTAGONAL")
      (footprint "TESTPOINT_OCTAGONAL")
      (libsource (lib "Miscellaneous") (part "TESTPOINT_OCTAGONAL"))
    )
    (comp (ref "TP60")
      (value "TESTPOINT_OCTAGONAL")
      (footprint "TESTPOINT_OCTAGONAL")
      (libsource (lib "") (part "TESTPOINT_OCTAGONAL_2"))
    )
    (comp (ref "TP61")
      (value "TESTPOINT_OCTAGONAL")
      (footprint "TESTPOINT_OCTAGONAL")
      (libsource (lib "Miscellaneous") (part "TESTPOINT_OCTAGONAL"))
    )
    (comp (ref "TP62")
      (value "TESTPOINT_OCTAGONAL")
      (footprint "TESTPOINT_OCTAGONAL")
      (libsource (lib "Miscellaneous") (part "TESTPOINT_OCTAGONAL"))
    )
    (comp (ref "TP63")
      (value "TESTPOINT_OCTAGONAL")
      (footprint "TESTPOINT_OCTAGONAL")
      (libsource (lib "") (part "TESTPOINT_OCTAGONAL_1"))
    )
    (comp (ref "TP64")
      (value "TESTPOINT_OCTAGONAL")
      (footprint "TESTPOINT_OCTAGONAL")
      (libsource (lib "Miscellaneous") (part "TESTPOINT_OCTAGONAL"))
    )
    (comp (ref "TP65")
      (value "TESTPOINT_OCTAGONAL")
      (footprint "TESTPOINT_OCTAGONAL")
      (libsource (lib "") (part "TESTPOINT_OCTAGONAL_1"))
    )
    (comp (ref "TP66")
      (value "TESTPOINT_OCTAGONAL")
      (footprint "TESTPOINT_OCTAGONAL")
      (libsource (lib "") (part "TESTPOINT_OCTAGONAL_1"))
    )
    (comp (ref "TP67")
      (value "TESTPOINT_OCTAGONAL")
      (footprint "TESTPOINT_OCTAGONAL")
      (libsource (lib "Miscellaneous") (part "TESTPOINT_OCTAGONAL"))
    )
    (comp (ref "TP68")
      (value "TESTPOINT_OCTAGONAL")
      (footprint "TESTPOINT_OCTAGONAL")
      (libsource (lib "") (part "TESTPOINT_OCTAGONAL_1"))
    )
    (comp (ref "TP69")
      (value "TESTPOINT_OCTAGONAL")
      (footprint "TESTPOINT_OCTAGONAL")
      (libsource (lib "") (part "TESTPOINT_OCTAGONAL_2"))
    )
    (comp (ref "TP70")
      (value "TESTPOINT_OCTAGONAL")
      (footprint "TESTPOINT_OCTAGONAL")
      (libsource (lib "Miscellaneous") (part "TESTPOINT_OCTAGONAL"))
    )
    (comp (ref "TP71")
      (value "TESTPOINT_OCTAGONAL")
      (footprint "TESTPOINT_OCTAGONAL")
      (libsource (lib "Miscellaneous") (part "TESTPOINT_OCTAGONAL"))
    )
    (comp (ref "TP72")
      (value "TESTPOINT_OCTAGONAL")
      (footprint "TESTPOINT_OCTAGONAL")
      (libsource (lib "") (part "TESTPOINT_OCTAGONAL_1"))
    )
    (comp (ref "TP73")
      (value "TESTPOINT_OCTAGONAL")
      (footprint "TESTPOINT_OCTAGONAL")
      (libsource (lib "") (part "TESTPOINT_OCTAGONAL_2"))
    )
    (comp (ref "TP74")
      (value "TESTPOINT_OCTAGONAL")
      (footprint "TESTPOINT_OCTAGONAL")
      (libsource (lib "Miscellaneous") (part "TESTPOINT_OCTAGONAL"))
    )
    (comp (ref "TP75")
      (value "TESTPOINT_OCTAGONAL")
      (footprint "TESTPOINT_OCTAGONAL")
      (libsource (lib "") (part "TESTPOINT_OCTAGONAL_1"))
    )
    (comp (ref "TP76")
      (value "TESTPOINT_OCTAGONAL")
      (footprint "TESTPOINT_OCTAGONAL")
      (libsource (lib "") (part "TESTPOINT_OCTAGONAL_3"))
    )
    (comp (ref "TP87")
      (value "TESTPOINT_OCTAGONAL")
      (footprint "TESTPOINT_OCTAGONAL")
      (libsource (lib "") (part "TESTPOINT_OCTAGONAL_2"))
    )
    (comp (ref "TP88")
      (value "TESTPOINT_OCTAGONAL")
      (footprint "TESTPOINT_OCTAGONAL")
      (libsource (lib "Miscellaneous") (part "TESTPOINT_OCTAGONAL"))
    )
    (comp (ref "TP89")
      (value "TESTPOINT_OCTAGONAL")
      (footprint "TESTPOINT_OCTAGONAL")
      (libsource (lib "") (part "TESTPOINT_OCTAGONAL_2"))
    )
    (comp (ref "TP92")
      (value "TESTPOINT_OCTAGONAL")
      (footprint "TESTPOINT_OCTAGONAL")
      (libsource (lib "") (part "TESTPOINT_OCTAGONAL_2"))
    )
    (comp (ref "TP93")
      (value "TESTPOINT_OCTAGONAL")
      (footprint "TESTPOINT_OCTAGONAL")
      (libsource (lib "") (part "TESTPOINT_OCTAGONAL_2"))
    )
    (comp (ref "TP94")
      (value "TESTPOINT_OCTAGONAL")
      (footprint "TESTPOINT_OCTAGONAL")
      (libsource (lib "") (part "TESTPOINT_OCTAGONAL_2"))
    )
    (comp (ref "TP95")
      (value "TESTPOINT_OCTAGONAL")
      (footprint "TESTPOINT_OCTAGONAL")
      (libsource (lib "") (part "TESTPOINT_OCTAGONAL_2"))
    )
    (comp (ref "TP96")
      (value "TESTPOINT_OCTAGONAL")
      (footprint "TESTPOINT_OCTAGONAL")
      (libsource (lib "") (part "TESTPOINT_OCTAGONAL_2"))
    )
    (comp (ref "TP97")
      (value "TESTPOINT_OCTAGONAL")
      (footprint "TESTPOINT_OCTAGONAL")
      (libsource (lib "") (part "TESTPOINT_OCTAGONAL_2"))
    )
    (comp (ref "TP98")
      (value "TESTPOINT_OCTAGONAL")
      (footprint "TESTPOINT_OCTAGONAL")
      (libsource (lib "") (part "TESTPOINT_OCTAGONAL_2"))
    )
    (comp (ref "TP102")
      (value "TESTPOINT_OCTAGONAL")
      (footprint "TESTPOINT_OCTAGONAL")
      (libsource (lib "") (part "TESTPOINT_OCTAGONAL_3"))
    )
    (comp (ref "TP103")
      (value "TESTPOINT_OCTAGONAL")
      (footprint "TESTPOINT_OCTAGONAL")
      (libsource (lib "") (part "TESTPOINT_OCTAGONAL_3"))
    )
    (comp (ref "TP104")
      (value "TESTPOINT_OCTAGONAL")
      (footprint "TESTPOINT_OCTAGONAL")
      (libsource (lib "") (part "TESTPOINT_OCTAGONAL_3"))
    )
    (comp (ref "TP105")
      (value "TESTPOINT_OCTAGONAL")
      (footprint "TESTPOINT_OCTAGONAL")
      (libsource (lib "") (part "TESTPOINT_OCTAGONAL_3"))
    )
    (comp (ref "TP106")
      (value "TESTPOINT_OCTAGONAL")
      (footprint "TESTPOINT_OCTAGONAL")
      (libsource (lib "") (part "TESTPOINT_OCTAGONAL_2"))
    )
    (comp (ref "TP107")
      (value "TESTPOINT_OCTAGONAL")
      (footprint "TESTPOINT_OCTAGONAL")
      (libsource (lib "") (part "TESTPOINT_OCTAGONAL_2"))
    )
    (comp (ref "TP108")
      (value "TESTPOINT_OCTAGONAL")
      (footprint "TESTPOINT_OCTAGONAL")
      (libsource (lib "") (part "TESTPOINT_OCTAGONAL_2"))
    )
    (comp (ref "TP109")
      (value "TESTPOINT_OCTAGONAL")
      (footprint "TESTPOINT_OCTAGONAL")
      (libsource (lib "") (part "TESTPOINT_OCTAGONAL_2"))
    )
    (comp (ref "TP110")
      (value "TESTPOINT_OCTAGONAL")
      (footprint "TESTPOINT_OCTAGONAL")
      (libsource (lib "") (part "TESTPOINT_OCTAGONAL_2"))
    )
    (comp (ref "TP111")
      (value "TESTPOINT_OCTAGONAL")
      (footprint "TESTPOINT_OCTAGONAL")
      (libsource (lib "") (part "TESTPOINT_OCTAGONAL_2"))
    )
    (comp (ref "TP112")
      (value "TESTPOINT_OCTAGONAL")
      (footprint "TESTPOINT_OCTAGONAL")
      (libsource (lib "") (part "TESTPOINT_OCTAGONAL_2"))
    )
    (comp (ref "TP113")
      (value "TESTPOINT_OCTAGONAL")
      (footprint "TESTPOINT_OCTAGONAL")
      (libsource (lib "") (part "TESTPOINT_OCTAGONAL_2"))
    )
    (comp (ref "TP114")
      (value "TESTPOINT_OCTAGONAL")
      (footprint "TESTPOINT_OCTAGONAL")
      (libsource (lib "") (part "TESTPOINT_OCTAGONAL_2"))
    )
    (comp (ref "TP115")
      (value "TESTPOINT_OCTAGONAL")
      (footprint "TESTPOINT_OCTAGONAL")
      (libsource (lib "Miscellaneous") (part "TESTPOINT_OCTAGONAL"))
    )
    (comp (ref "TP116")
      (value "TESTPOINT_OCTAGONAL")
      (footprint "TESTPOINT_OCTAGONAL")
      (libsource (lib "Miscellaneous") (part "TESTPOINT_OCTAGONAL"))
    )
    (comp (ref "TP117")
      (value "TESTPOINT_OCTAGONAL")
      (footprint "TESTPOINT_OCTAGONAL")
      (libsource (lib "Miscellaneous") (part "TESTPOINT_OCTAGONAL"))
    )
    (comp (ref "TP118")
      (value "TESTPOINT_OCTAGONAL")
      (footprint "TESTPOINT_OCTAGONAL")
      (libsource (lib "Miscellaneous") (part "TESTPOINT_OCTAGONAL"))
    )
    (comp (ref "TP119")
      (value "TESTPOINT_OCTAGONAL")
      (footprint "TESTPOINT_OCTAGONAL")
      (libsource (lib "Miscellaneous") (part "TESTPOINT_OCTAGONAL"))
    )
    (comp (ref "TP120")
      (value "TESTPOINT_OCTAGONAL")
      (footprint "TESTPOINT_OCTAGONAL")
      (libsource (lib "Miscellaneous") (part "TESTPOINT_OCTAGONAL"))
    )
    (comp (ref "TP121")
      (value "TESTPOINT_OCTAGONAL")
      (footprint "TESTPOINT_OCTAGONAL")
      (libsource (lib "Miscellaneous") (part "TESTPOINT_OCTAGONAL"))
    )
    (comp (ref "TP122")
      (value "TESTPOINT_OCTAGONAL")
      (footprint "TESTPOINT_OCTAGONAL")
      (libsource (lib "Miscellaneous") (part "TESTPOINT_OCTAGONAL"))
    )
    (comp (ref "TP180")
      (value "TESTPOINT_OCTAGONAL")
      (footprint "TESTPOINT_OCTAGONAL")
      (libsource (lib "") (part "TESTPOINT_OCTAGONAL_1"))
    )
    (comp (ref "TP181")
      (value "TESTPOINT_OCTAGONAL")
      (footprint "TESTPOINT_OCTAGONAL")
      (libsource (lib "") (part "TESTPOINT_OCTAGONAL_3"))
    )
    (comp (ref "TP182")
      (value "TESTPOINT_OCTAGONAL")
      (footprint "TESTPOINT_OCTAGONAL")
      (libsource (lib "") (part "TESTPOINT_OCTAGONAL_1"))
    )
    (comp (ref "TP183")
      (value "TESTPOINT_OCTAGONAL")
      (footprint "TESTPOINT_OCTAGONAL")
      (libsource (lib "") (part "TESTPOINT_OCTAGONAL_1"))
    )
    (comp (ref "TP188")
      (value "TESTPOINT_OCTAGONAL")
      (footprint "TESTPOINT_OCTAGONAL")
      (libsource (lib "") (part "TESTPOINT_OCTAGONAL_2"))
    )
    (comp (ref "TP189")
      (value "TESTPOINT_OCTAGONAL")
      (footprint "TESTPOINT_OCTAGONAL")
      (libsource (lib "") (part "TESTPOINT_OCTAGONAL_1"))
    )
    (comp (ref "TP190")
      (value "TESTPOINT_OCTAGONAL")
      (footprint "TESTPOINT_OCTAGONAL")
      (libsource (lib "Miscellaneous") (part "TESTPOINT_OCTAGONAL"))
    )
    (comp (ref "TP191")
      (value "TESTPOINT_ROUND")
      (footprint "TESTPOINT_ROUND")
      (libsource (lib "Miscellaneous") (part "TESTPOINT_ROUND"))
    )
    (comp (ref "TP192")
      (value "TESTPOINT_OCTAGONAL")
      (footprint "TESTPOINT_OCTAGONAL")
      (libsource (lib "") (part "TESTPOINT_OCTAGONAL_2"))
    )
    (comp (ref "TP193")
      (value "TESTPOINT_OCTAGONAL")
      (footprint "TESTPOINT_OCTAGONAL")
      (libsource (lib "") (part "TESTPOINT_OCTAGONAL_3"))
    )
    (comp (ref "U1")
      (value "STM32F103RG")
      (footprint "STM_STM32F103RG_LQFP64:TSQFP50P1200X1200X160-64N")
      (description "IC MCU 32BIT 1MB FLASH 64LQFP")
      (fields
        (field (name "MANUFACTURER") "STMicroelectronics")
        (field (name "MANUFACTURER PART NUMBER") "STM32F103RGT6")
      )
      (libsource (lib "IntegratedCircuits_Embedded_Microcontrollers") (part "STM_STM32F103RG_LQFP64"))
    )
    (comp (ref "U2")
      (value "M24M02")
      (footprint "STM_M24M02-DR_SOIC8:SOIC127P600X175-8N")
      (description "IC EEPROM 2MBIT I2C 1MHZ 8SO")
      (fields
        (field (name "MANUFACTURER") "STMicroelectronics")
        (field (name "MANUFACTURER PART NUMBER") "M24M02-DRMN6TP")
      )
      (libsource (lib "IntegratedCircuits_Memory_EEPROM") (part "STM_M24M02-DR_SOIC8"))
    )
    (comp (ref "U3")
      (value "M24M02")
      (footprint "STM_M24M02-DR_SOIC8:SOIC127P600X175-8N")
      (description "IC EEPROM 2MBIT I2C 1MHZ 8SO")
      (fields
        (field (name "MANUFACTURER") "STMicroelectronics")
        (field (name "MANUFACTURER PART NUMBER") "M24M02-DRMN6TP")
      )
      (libsource (lib "IntegratedCircuits_Memory_EEPROM") (part "STM_M24M02-DR_SOIC8"))
    )
    (comp (ref "U5")
      (value "SP6205EM5-L")
      (footprint "EXAR_SP6205EM5-L_SOT23_5:SOT95P280X145-5N")
      (description "IC REG LIN POS ADJ 500MA SOT23-5")
      (fields (field (name "MANUFACTURER") "Exar") (field (name "MANUFACTURER PART NUMBER") "SP6205EM5-L/TR"))
      (libsource (lib "IntegratedCircuits_Power_VoltageRegsLinear") (part "EXAR_SP6205EM5-L_SOT23_5"))
    )
    (comp (ref "U6")
      (value "SP6205EM5-L")
      (footprint "EXAR_SP6205EM5-L_SOT23_5:SOT95P280X145-5N")
      (description "IC REG LIN POS ADJ 500MA SOT23-5")
      (fields (field (name "MANUFACTURER") "Exar") (field (name "MANUFACTURER PART NUMBER") "SP6205EM5-L/TR"))
      (libsource (lib "IntegratedCircuits_Power_VoltageRegsLinear") (part "EXAR_SP6205EM5-L_SOT23_5"))
    )
    (comp (ref "U7")
      (value "FT230XS")
      (footprint "FTDI_FT230XS_SOP64P600X175-16N")
      (description "IC USB SERIAL BASIC UART 16SSOP")
      (fields (field (name "MANUFACTURER") "FTDI") (field (name "MANUFACTURER PART NUMBER") "FT230XS-U"))
      (libsource (lib "IntegratedCircuits_Interface_RSType") (part "FTDI_FT230XS_SSOP16"))
    )
    (comp (ref "U35")
      (value "SP6205EM5-L-3-3/TR")
      (footprint "MAXLINEAR_SP6205EM5-L-3-3/TR_SOT23_5:SOT95P280X100-5N")
      (description "IC REG LINEAR 3.3V 500MA SOT23-5")
      (fields (field (name "MANUFACTURER") "Exar"))
      (libsource (lib "IntegratedCircuits_Power_VoltageRegsLinear") (part "MAXLINEAR_SP6205EM5-L-3-3/TR_SOT23_5"))
    )
    (comp (ref "V1")
      (value "5V Cont / 150V Trip")
      (footprint "BOURNS_CGA0603MLC:INDC1608X04N")
      (description "VARISTOR 0603")
      (fields
        (field (name "MANUFACTURER") "Bourns")
        (field (name "MANUFACTURER PART NUMBER") "CG0603MLC-05E")
      )
      (libsource (lib "CircuitProtection_Varistors") (part "BOURNS_CGA0603MLC"))
    )
    (comp (ref "V2")
      (value "5V Cont / 150V Trip")
      (footprint "BOURNS_CGA0603MLC:INDC1608X04N")
      (description "VARISTOR 0603")
      (fields
        (field (name "MANUFACTURER") "Bourns")
        (field (name "MANUFACTURER PART NUMBER") "CG0603MLC-05E")
      )
      (libsource (lib "CircuitProtection_Varistors") (part "BOURNS_CGA0603MLC"))
    )
    (comp (ref "V3")
      (value "5V Cont / 150V Trip")
      (footprint "BOURNS_CGA0603MLC:INDC1608X04N")
      (description "VARISTOR 0603")
      (fields
        (field (name "MANUFACTURER") "Bourns")
        (field (name "MANUFACTURER PART NUMBER") "CG0603MLC-05E")
      )
      (libsource (lib "CircuitProtection_Varistors") (part "BOURNS_CGA0603MLC"))
    )
    (comp (ref "X1")
      (value "8MHz")
      (footprint "MURATA_CSTNE8M00G550000R0")
      (description "CERAMIC RES 8.0000MHZ 33PF SMD")
      (fields
        (field (name "MANUFACTURER") "Murata")
        (field (name "MANUFACTURER PART NUMBER") "CSTNE8M00G550000R0")
      )
      (libsource (lib "PassiveComponents_Oscillators_Resonators") (part "MURATA_CSTNE8M00G550000R0"))
    )
    (comp (ref "X3")
      (value "32768Hz")
      (footprint "EPSON_MC-146")
      (description "CRYSTAL 32.7680KHZ 12.5PF SMD")
      (fields
        (field (name "MANUFACTURER") "Epson")
        (field (name "MANUFACTURER PART NUMBER") "MC-14632.7680KA-A0:ROHS")
      )
      (libsource (lib "PassiveComponents_Oscillators_Resonators") (part "EPSON_MC-146"))
    )
  )
  (nets
    (net (code "1") (name "/5VUSB_CON") (class "Default")
      (node (ref "M1") (pin "A9") (pinfunction "CC_IO12_SPARE_A9") (pintype "passive"))
      (node (ref "Q6") (pin "1") (pinfunction "G_1") (pintype "passive"))
      (node (ref "R20") (pin "2") (pinfunction "2_2") (pintype "passive"))
      (node (ref "TP32") (pin "1") (pinfunction "1_1") (pintype "passive"))
      (node (ref "U1") (pin "9") (pinfunction "PC1_9") (pintype "bidirectional"))
    )
    (net (code "2") (name "/10ms") (class "Default")
      (node (ref "TP191") (pin "1") (pinfunction "1_1") (pintype "passive"))
      (node (ref "U1") (pin "40") (pinfunction "PC9_40") (pintype "bidirectional"))
    )
    (net (code "3") (name "/AP_MODE") (class "Default")
      (node (ref "M1") (pin "C11") (pinfunction "AP_MODE_C11") (pintype "passive"))
      (node (ref "TP112") (pin "1") (pinfunction "1_1") (pintype "passive"))
      (node (ref "U1") (pin "61") (pinfunction "PB8_61") (pintype "bidirectional"))
    )
    (net (code "4") (name "/BOOT0") (class "Default")
      (node (ref "R3") (pin "2") (pinfunction "2_2") (pintype "passive"))
      (node (ref "SW1A") (pin "2") (pinfunction "2_2") (pintype "passive"))
      (node (ref "TP48") (pin "1") (pinfunction "1_1") (pintype "passive"))
      (node (ref "U1") (pin "60") (pinfunction "BOOT_60") (pintype "passive"))
    )
    (net (code "5") (name "/BOOT1") (class "Default")
      (node (ref "R4") (pin "1") (pinfunction "1_1") (pintype "passive"))
      (node (ref "SW1B") (pin "1") (pinfunction "1_1") (pintype "passive"))
      (node (ref "TP19") (pin "1") (pinfunction "1_1") (pintype "passive"))
      (node (ref "U1") (pin "28") (pinfunction "PB2_28") (pintype "bidirectional"))
    )
    (net (code "6") (name "/CC_IO00_SPARE") (class "Default")
      (node (ref "M1") (pin "C10") (pinfunction "CC_IO00_SPARE_C10") (pintype "passive"))
      (node (ref "TP98") (pin "1") (pinfunction "1_1") (pintype "passive"))
      (node (ref "U1") (pin "8") (pinfunction "PC0_8") (pintype "bidirectional"))
    )
    (net (code "7") (name "/CC_IO03_SPARE") (class "Default")
      (node (ref "M1") (pin "C7") (pinfunction "CC_IO03_SPARE_C7") (pintype "passive"))
      (node (ref "TP97") (pin "1") (pinfunction "1_1") (pintype "passive"))
      (node (ref "U1") (pin "15") (pinfunction "PA1_15") (pintype "bidirectional"))
    )
    (net (code "8") (name "/CC_IO04_SPARE") (class "Default")
      (node (ref "M1") (pin "C6") (pinfunction "CC_IO04_SPARE_C6") (pintype "passive"))
      (node (ref "TP96") (pin "1") (pinfunction "1_1") (pintype "passive"))
      (node (ref "U1") (pin "29") (pinfunction "PB10_29") (pintype "bidirectional"))
    )
    (net (code "9") (name "/CC_IO05_SPARE") (class "Default")
      (node (ref "M1") (pin "C5") (pinfunction "CC_IO05_SPARE_C5") (pintype "passive"))
      (node (ref "TP95") (pin "1") (pinfunction "1_1") (pintype "passive"))
      (node (ref "U1") (pin "30") (pinfunction "PB11_30") (pintype "bidirectional"))
    )
    (net (code "10") (name "/CC_IO06_SPARE") (class "Default")
      (node (ref "M1") (pin "C4") (pinfunction "CC_IO06_SPARE_C4") (pintype "passive"))
      (node (ref "TP94") (pin "1") (pinfunction "1_1") (pintype "passive"))
      (node (ref "U1") (pin "45") (pinfunction "PA12_45") (pintype "bidirectional"))
    )
    (net (code "11") (name "/CC_IO08_SPARE") (class "Default")
      (node (ref "M1") (pin "C2") (pinfunction "CC_IO08_SPARE_C2") (pintype "passive"))
      (node (ref "TP93") (pin "1") (pinfunction "1_1") (pintype "passive"))
      (node (ref "U1") (pin "44") (pinfunction "PA11_44") (pintype "bidirectional"))
    )
    (net (code "12") (name "/CC_IO09_SPARE") (class "Default")
      (node (ref "M1") (pin "C1") (pinfunction "CC_IO09_SPARE_C1") (pintype "passive"))
      (node (ref "TP92") (pin "1") (pinfunction "1_1") (pintype "passive"))
      (node (ref "U1") (pin "41") (pinfunction "PA8_41") (pintype "bidirectional"))
    )
    (net (code "13") (name "/CC_IO22_SPARE") (class "Default")
      (node (ref "M1") (pin "A11") (pinfunction "CC_IO22_SPARE_A11") (pintype "passive"))
      (node (ref "TP89") (pin "1") (pinfunction "1_1") (pintype "passive"))
      (node (ref "U1") (pin "52") (pinfunction "PC11_52") (pintype "bidirectional"))
    )
    (net (code "14") (name "/CC_IO28_SPARE") (class "Default")
      (node (ref "M1") (pin "B2") (pinfunction "CC_IO28_SPARE_B2") (pintype "passive"))
      (node (ref "TP88") (pin "1") (pinfunction "1_1") (pintype "passive"))
      (node (ref "U1") (pin "51") (pinfunction "PC10_51") (pintype "bidirectional"))
    )
    (net (code "15") (name "/CC_JTAG_TCK") (class "Default")
      (node (ref "CN1W") (pin "9") (pinfunction "9_9") (pintype "passive"))
      (node (ref "M1") (pin "B3") (pinfunction "CC_JTAG_TCK_B3") (pintype "passive"))
      (node (ref "TP121") (pin "1") (pinfunction "1_1") (pintype "passive"))
    )
    (net (code "16") (name "/CC_JTAG_TDI") (class "Default")
      (node (ref "CN1W") (pin "2") (pinfunction "2_2") (pintype "passive"))
      (node (ref "M1") (pin "A12") (pinfunction "CC_JTAG_TDI_A12") (pintype "passive"))
      (node (ref "TP115") (pin "1") (pinfunction "1_1") (pintype "passive"))
    )
    (net (code "17") (name "/CC_JTAG_TDO") (class "Default")
      (node (ref "CN1W") (pin "4") (pinfunction "4_4") (pintype "passive"))
      (node (ref "M1") (pin "B1") (pinfunction "CC_JTAG_TDO_B1") (pintype "passive"))
      (node (ref "TP117") (pin "1") (pinfunction "1_1") (pintype "passive"))
    )
    (net (code "18") (name "/CC_JTAG_TMS") (class "Default")
      (node (ref "CN1W") (pin "3") (pinfunction "3_3") (pintype "passive"))
      (node (ref "M1") (pin "B4") (pinfunction "CC_JTAG_TMS_B4") (pintype "passive"))
      (node (ref "TP116") (pin "1") (pinfunction "1_1") (pintype "passive"))
    )
    (net (code "19") (name "/CC_PGM") (class "Default")
      (node (ref "CN1W") (pin "8") (pinfunction "8_8") (pintype "passive"))
      (node (ref "M1") (pin "B5") (pinfunction "CC_PGM_B5") (pintype "passive"))
      (node (ref "TP120") (pin "1") (pinfunction "1_1") (pintype "passive"))
      (node (ref "U1") (pin "11") (pinfunction "PC3_11") (pintype "bidirectional"))
    )
    (net (code "20") (name "/CC_RST#") (class "Default")
      (node (ref "CN1W") (pin "6") (pinfunction "6_6") (pintype "passive"))
      (node (ref "M1") (pin "C12") (pinfunction "CC_RST#_C12") (pintype "passive"))
      (node (ref "R103") (pin "1") (pinfunction "1_1") (pintype "passive"))
      (node (ref "TP119") (pin "1") (pinfunction "1_1") (pintype "passive"))
    )
    (net (code "21") (name "/CC_SWD") (class "Default")
      (node (ref "M1") (pin "C13") (pinfunction "CC_SWD_C13") (pintype "passive"))
      (node (ref "TP114") (pin "1") (pinfunction "1_1") (pintype "passive"))
      (node (ref "U1") (pin "10") (pinfunction "PC2_10") (pintype "bidirectional"))
    )
    (net (code "22") (name "/EEP_WC#") (class "Default")
      (node (ref "M1") (pin "C3") (pinfunction "EXT_EEP_WC#_C3") (pintype "passive"))
      (node (ref "R9") (pin "1") (pinfunction "1_1") (pintype "passive"))
      (node (ref "TP25") (pin "1") (pinfunction "1_1") (pintype "passive"))
      (node (ref "U1") (pin "14") (pinfunction "PA0-WKUP_14") (pintype "bidirectional"))
      (node (ref "U2") (pin "7") (pinfunction "~{WC}_7") (pintype "input"))
      (node (ref "U3") (pin "7") (pinfunction "~{WC}_7") (pintype "input"))
    )
    (net (code "23") (name "/FT800_CS#") (class "Default")
      (node (ref "U1") (pin "24") (pinfunction "PC4_24") (pintype "bidirectional"))
    )
    (net (code "24") (name "/FT800_INT#") (class "Default")
      (node (ref "U1") (pin "20") (pinfunction "PA4_20") (pintype "bidirectional"))
    )
    (net (code "25") (name "/FT800_MISO") (class "Default")
      (node (ref "U1") (pin "22") (pinfunction "PA6_22") (pintype "bidirectional"))
    )
    (net (code "26") (name "/FT800_MOSI") (class "Default")
      (node (ref "U1") (pin "23") (pinfunction "PA7_23") (pintype "bidirectional"))
    )
    (net (code "27") (name "/FT800_PD#") (class "Default")
      (node (ref "U1") (pin "25") (pinfunction "PC5_25") (pintype "bidirectional"))
    )
    (net (code "28") (name "/FT800_SCK") (class "Default")
      (node (ref "U1") (pin "21") (pinfunction "PA5_21") (pintype "bidirectional"))
    )
    (net (code "29") (name "/FTDI_RX") (class "Default")
      (node (ref "CN1W") (pin "5") (pinfunction "5_5") (pintype "passive"))
      (node (ref "M1") (pin "C9") (pinfunction "FTDI_RX_C9") (pintype "passive"))
      (node (ref "TP118") (pin "1") (pinfunction "1_1") (pintype "passive"))
    )
    (net (code "30") (name "/FTDI_TX") (class "Default")
      (node (ref "CN1W") (pin "10") (pinfunction "10_10") (pintype "passive"))
      (node (ref "M1") (pin "C8") (pinfunction "FTDI_TX_C8") (pintype "passive"))
      (node (ref "TP122") (pin "1") (pinfunction "1_1") (pintype "passive"))
    )
    (net (code "31") (name "/I2C_SCL") (class "Default")
      (node (ref "CN1S") (pin "10") (pinfunction "10_10") (pintype "passive"))
      (node (ref "M1") (pin "A3") (pinfunction "EXT_I2C_SCL_A3") (pintype "passive"))
      (node (ref "R8") (pin "1") (pinfunction "1_1") (pintype "passive"))
      (node (ref "TP23") (pin "1") (pinfunction "1_1") (pintype "passive"))
      (node (ref "U1") (pin "58") (pinfunction "PB6_58") (pintype "bidirectional"))
      (node (ref "U2") (pin "6") (pinfunction "SCL_6") (pintype "open_collector"))
      (node (ref "U3") (pin "6") (pinfunction "SCL_6") (pintype "open_collector"))
    )
    (net (code "32") (name "/I2C_SDA") (class "Default")
      (node (ref "CN1S") (pin "5") (pinfunction "5_5") (pintype "passive"))
      (node (ref "M1") (pin "A4") (pinfunction "EXT_I2C_SDA_A4") (pintype "passive"))
      (node (ref "R7") (pin "1") (pinfunction "1_1") (pintype "passive"))
      (node (ref "TP24") (pin "1") (pinfunction "1_1") (pintype "passive"))
      (node (ref "U1") (pin "59") (pinfunction "PB7_59") (pintype "bidirectional"))
      (node (ref "U2") (pin "5") (pinfunction "SDA_5") (pintype "open_collector"))
      (node (ref "U3") (pin "5") (pinfunction "SDA_5") (pintype "open_collector"))
    )
    (net (code "33") (name "/MON_12VPWR") (class "Default")
      (node (ref "M1") (pin "A10") (pinfunction "CC_IO13_SPARE_A10") (pintype "passive"))
      (node (ref "R14") (pin "1") (pinfunction "1_1") (pintype "passive"))
      (node (ref "R15") (pin "2") (pinfunction "2_2") (pintype "passive"))
      (node (ref "TP34") (pin "1") (pinfunction "1_1") (pintype "passive"))
      (node (ref "U1") (pin "2") (pinfunction "PC13-TAMPER/RTC_2") (pintype "bidirectional"))
    )
    (net (code "34") (name "/PWREN#") (class "Default")
      (node (ref "R23") (pin "1") (pinfunction "1_1") (pintype "passive"))
      (node (ref "TP65") (pin "1") (pinfunction "1_1") (pintype "passive"))
      (node (ref "U7") (pin "16") (pinfunction "CBUS3_16") (pintype "passive"))
    )
    (net (code "35") (name "/ST_JTAG_TCK") (class "Default")
      (node (ref "CN1S") (pin "9") (pinfunction "9_9") (pintype "passive"))
      (node (ref "TP15") (pin "1") (pinfunction "1_1") (pintype "passive"))
      (node (ref "U1") (pin "49") (pinfunction "PA14_49") (pintype "bidirectional"))
    )
    (net (code "36") (name "/ST_JTAG_TDI") (class "Default")
      (node (ref "CN1S") (pin "8") (pinfunction "8_8") (pintype "passive"))
      (node (ref "TP16") (pin "1") (pinfunction "1_1") (pintype "passive"))
      (node (ref "U1") (pin "50") (pinfunction "PA15_50") (pintype "bidirectional"))
    )
    (net (code "37") (name "/ST_JTAG_TDO") (class "Default")
      (node (ref "CN1S") (pin "4") (pinfunction "4_4") (pintype "passive"))
      (node (ref "TP20") (pin "1") (pinfunction "1_1") (pintype "passive"))
      (node (ref "U1") (pin "55") (pinfunction "PB3_55") (pintype "bidirectional"))
    )
    (net (code "38") (name "/ST_JTAG_TMS") (class "Default")
      (node (ref "CN1S") (pin "3") (pinfunction "3_3") (pintype "passive"))
      (node (ref "TP14") (pin "1") (pinfunction "1_1") (pintype "passive"))
      (node (ref "U1") (pin "46") (pinfunction "PA13_46") (pintype "bidirectional"))
    )
    (net (code "39") (name "/ST_JTAG_TRST#") (class "Default")
      (node (ref "CN1S") (pin "2") (pinfunction "2_2") (pintype "passive"))
      (node (ref "TP21") (pin "1") (pinfunction "1_1") (pintype "passive"))
      (node (ref "U1") (pin "56") (pinfunction "PB4_56") (pintype "bidirectional"))
    )
    (net (code "40") (name "/ST_RST#") (class "Default")
      (node (ref "C8") (pin "2") (pinfunction "2_2") (pintype "passive"))
      (node (ref "CN1S") (pin "6") (pinfunction "6_6") (pintype "passive"))
      (node (ref "TP49") (pin "1") (pinfunction "1_1") (pintype "passive"))
      (node (ref "U1") (pin "7") (pinfunction "NRST_7") (pintype "bidirectional"))
    )
    (net (code "41") (name "/ST_SPI2_MISO") (class "Default")
      (node (ref "R82") (pin "2") (pinfunction "2_2") (pintype "passive"))
      (node (ref "TP107") (pin "1") (pinfunction "1_1") (pintype "passive"))
      (node (ref "U1") (pin "34") (pinfunction "PB13_34") (pintype "bidirectional"))
    )
    (net (code "42") (name "/ST_SPI2_MOSI") (class "Default")
      (node (ref "R81") (pin "2") (pinfunction "2_2") (pintype "passive"))
      (node (ref "TP108") (pin "1") (pinfunction "1_1") (pintype "passive"))
      (node (ref "U1") (pin "33") (pinfunction "PB12_33") (pintype "bidirectional"))
    )
    (net (code "43") (name "/ST_SPI2_NSS") (class "Default")
      (node (ref "R79") (pin "2") (pinfunction "2_2") (pintype "passive"))
      (node (ref "TP110") (pin "1") (pinfunction "1_1") (pintype "passive"))
      (node (ref "U1") (pin "36") (pinfunction "PB15_36") (pintype "bidirectional"))
    )
    (net (code "44") (name "/ST_SPI2_SCK") (class "Default")
      (node (ref "R83") (pin "2") (pinfunction "2_2") (pintype "passive"))
      (node (ref "TP106") (pin "1") (pinfunction "1_1") (pintype "passive"))
      (node (ref "U1") (pin "35") (pinfunction "PB14_35") (pintype "bidirectional"))
    )
    (net (code "45") (name "/ST_UART2_RX") (class "Default")
      (node (ref "R80") (pin "2") (pinfunction "2_2") (pintype "passive"))
      (node (ref "TP109") (pin "1") (pinfunction "1_1") (pintype "passive"))
      (node (ref "U1") (pin "17") (pinfunction "PA3_17") (pintype "bidirectional"))
    )
    (net (code "46") (name "/ST_UART2_TX") (class "Default")
      (node (ref "R78") (pin "2") (pinfunction "2_2") (pintype "passive"))
      (node (ref "TP111") (pin "1") (pinfunction "1_1") (pintype "passive"))
      (node (ref "U1") (pin "16") (pinfunction "PA2_16") (pintype "bidirectional"))
    )
    (net (code "47") (name "/THM_MES") (class "Default")
      (node (ref "C12") (pin "2") (pinfunction "2_2") (pintype "passive"))
      (node (ref "R5") (pin "2") (pinfunction "2_2") (pintype "passive"))
      (node (ref "TH1") (pin "1") (pinfunction "1_1") (pintype "passive"))
      (node (ref "TP18") (pin "1") (pinfunction "1_1") (pintype "passive"))
      (node (ref "U1") (pin "27") (pinfunction "PB1_27") (pintype "bidirectional"))
    )
    (net (code "48") (name "/TWB_PWR") (class "Default")
      (node (ref "U1") (pin "38") (pinfunction "PC7_38") (pintype "bidirectional"))
    )
    (net (code "49") (name "/TWB_RX") (class "Default")
      (node (ref "U1") (pin "54") (pinfunction "PD2_54") (pintype "bidirectional"))
    )
    (net (code "50") (name "/TWB_TX") (class "Default")
      (node (ref "U1") (pin "53") (pinfunction "PC12_53") (pintype "bidirectional"))
    )
    (net (code "51") (name "/USB_RX") (class "Default")
      (node (ref "TP10") (pin "1") (pinfunction "1_1") (pintype "passive"))
      (node (ref "U1") (pin "42") (pinfunction "PA9_42") (pintype "bidirectional"))
      (node (ref "U7") (pin "4") (pinfunction "RxD_4") (pintype "passive"))
    )
    (net (code "52") (name "/USB_TX") (class "Default")
      (node (ref "TP11") (pin "1") (pinfunction "1_1") (pintype "passive"))
      (node (ref "U1") (pin "43") (pinfunction "PA10_43") (pintype "bidirectional"))
      (node (ref "U7") (pin "1") (pinfunction "TxD_1") (pintype "passive"))
    )
    (net (code "53") (name "/Vddmes") (class "Default")
      (node (ref "TH1") (pin "2") (pinfunction "2_2") (pintype "passive"))
      (node (ref "TP17") (pin "1") (pinfunction "1_1") (pintype "passive"))
      (node (ref "U1") (pin "26") (pinfunction "PB0_26") (pintype "bidirectional"))
    )
    (net (code "54") (name "/WIFI_DETECT") (class "Default")
      (node (ref "M1") (pin "C18") (pinfunction "DETECT-OT_C18") (pintype "passive"))
      (node (ref "R105") (pin "2") (pinfunction "2_2") (pintype "passive"))
      (node (ref "TP189") (pin "1") (pinfunction "1_1") (pintype "passive"))
      (node (ref "U1") (pin "37") (pinfunction "PC6_37") (pintype "bidirectional"))
    )
    (net (code "55") (name "/WIFI_PWR") (class "Default")
      (node (ref "R101") (pin "1") (pinfunction "1_1") (pintype "passive"))
      (node (ref "R102") (pin "1") (pinfunction "1_1") (pintype "passive"))
      (node (ref "TP113") (pin "1") (pinfunction "1_1") (pintype "passive"))
      (node (ref "U1") (pin "62") (pinfunction "PB9_62") (pintype "bidirectional"))
    )
    (net (code "56") (name "3V3") (class "Default")
      (node (ref "C1") (pin "1") (pinfunction "1_1") (pintype "passive"))
      (node (ref "C10") (pin "1") (pinfunction "1_1") (pintype "passive"))
      (node (ref "C13") (pin "2") (pinfunction "2_2") (pintype "passive"))
      (node (ref "C14") (pin "2") (pinfunction "2_2") (pintype "passive"))
      (node (ref "C2") (pin "1") (pinfunction "1_1") (pintype "passive"))
      (node (ref "C3") (pin "1") (pinfunction "1_1") (pintype "passive"))
      (node (ref "C4") (pin "1") (pinfunction "1_1") (pintype "passive"))
      (node (ref "C5") (pin "1") (pinfunction "1_1") (pintype "passive"))
      (node (ref "C9") (pin "1") (pinfunction "1_1") (pintype "passive"))
      (node (ref "CN1S") (pin "7") (pinfunction "7_7") (pintype "passive"))
      (node (ref "CN1W") (pin "7") (pinfunction "7_7") (pintype "passive"))
      (node (ref "D1") (pin "2") (pinfunction "A_2") (pintype "passive"))
      (node (ref "D3") (pin "1") (pinfunction "K_1") (pintype "passive"))
      (node (ref "D4") (pin "1") (pinfunction "K_1") (pintype "passive"))
      (node (ref "M1") (pin "C17") (pinfunction "DETECT-IN_C17") (pintype "passive"))
      (node (ref "R1") (pin "1") (pinfunction "1_1") (pintype "passive"))
      (node (ref "R104") (pin "1") (pinfunction "1_1") (pintype "passive"))
      (node (ref "R4") (pin "2") (pinfunction "2_2") (pintype "passive"))
      (node (ref "R7") (pin "2") (pinfunction "2_2") (pintype "passive"))
      (node (ref "R8") (pin "2") (pinfunction "2_2") (pintype "passive"))
      (node (ref "R9") (pin "2") (pinfunction "2_2") (pintype "passive"))
      (node (ref "SW1A") (pin "1") (pinfunction "1_1") (pintype "passive"))
      (node (ref "TP76") (pin "1") (pinfunction "1_1") (pintype "passive"))
      (node (ref "U1") (pin "13") (pinfunction "VDDA_13") (pintype "power_in"))
      (node (ref "U1") (pin "18") (pinfunction "VSS_4_18") (pintype "power_in"))
      (node (ref "U1") (pin "32") (pinfunction "VDD_1_32") (pintype "power_in"))
      (node (ref "U1") (pin "48") (pinfunction "VDD_2_48") (pintype "power_in"))
      (node (ref "U1") (pin "64") (pinfunction "VDD_3_64") (pintype "power_in"))
      (node (ref "U2") (pin "8") (pinfunction "Vcc_8") (pintype "power_in"))
      (node (ref "U3") (pin "3") (pinfunction "E2_3") (pintype "passive"))
      (node (ref "U3") (pin "8") (pinfunction "Vcc_8") (pintype "power_in"))
    )
    (net (code "57") (name "3V3WIFI") (class "Default")
      (node (ref "C81") (pin "1") (pinfunction "1_1") (pintype "passive"))
      (node (ref "R106") (pin "2") (pinfunction "2_2") (pintype "passive"))
      (node (ref "TP192") (pin "1") (pinfunction "1_1") (pintype "passive"))
      (node (ref "U35") (pin "5") (pinfunction "Vout_5") (pintype "passive"))
    )
    (net (code "58") (name "4V") (class "Default")
      (node (ref "C16") (pin "2") (pinfunction "2_2") (pintype "passive"))
      (node (ref "D3") (pin "2") (pinfunction "A_2") (pintype "passive"))
      (node (ref "R11") (pin "2") (pinfunction "2_2") (pintype "passive"))
      (node (ref "TP71") (pin "1") (pinfunction "1_1") (pintype "passive"))
      (node (ref "U5") (pin "5") (pinfunction "VOUT_5") (pintype "passive"))
    )
    (net (code "59") (name "4VUSB") (class "Default")
      (node (ref "C18") (pin "2") (pinfunction "2_2") (pintype "passive"))
      (node (ref "D4") (pin "2") (pinfunction "A_2") (pintype "passive"))
      (node (ref "R16") (pin "2") (pinfunction "2_2") (pintype "passive"))
      (node (ref "TP70") (pin "1") (pinfunction "1_1") (pintype "passive"))
      (node (ref "U6") (pin "5") (pinfunction "VOUT_5") (pintype "passive"))
    )
    (net (code "60") (name "5V") (class "Default")
      (node (ref "C17") (pin "2") (pinfunction "2_2") (pintype "passive"))
      (node (ref "C79") (pin "1") (pinfunction "1_1") (pintype "passive"))
      (node (ref "C82") (pin "1") (pinfunction "1_1") (pintype "passive"))
      (node (ref "Q7") (pin "3") (pinfunction "D_3") (pintype "passive"))
      (node (ref "R100") (pin "2") (pinfunction "2_2") (pintype "passive"))
      (node (ref "R99") (pin "1") (pinfunction "1_1") (pintype "passive"))
      (node (ref "TP74") (pin "1") (pinfunction "1_1") (pintype "passive"))
      (node (ref "U35") (pin "1") (pinfunction "Vin_1") (pintype "passive"))
      (node (ref "U5") (pin "1") (pinfunction "VIN_1") (pintype "passive"))
    )
    (net (code "61") (name "5VUSB") (class "Default")
      (node (ref "C19") (pin "2") (pinfunction "2_2") (pintype "passive"))
      (node (ref "C20") (pin "1") (pinfunction "1_1") (pintype "passive"))
      (node (ref "C21") (pin "2") (pinfunction "2_2") (pintype "passive"))
      (node (ref "Q1") (pin "3") (pinfunction "D_3") (pintype "passive"))
      (node (ref "Q7") (pin "2") (pinfunction "S_2") (pintype "passive"))
      (node (ref "R19") (pin "1") (pinfunction "1_1") (pintype "passive"))
      (node (ref "R21") (pin "1") (pinfunction "1_1") (pintype "passive"))
      (node (ref "TP67") (pin "1") (pinfunction "1_1") (pintype "passive"))
      (node (ref "U6") (pin "1") (pinfunction "VIN_1") (pintype "passive"))
    )
    (net (code "62") (name "12V") (class "Default")
      (node (ref "R14") (pin "2") (pinfunction "2_2") (pintype "passive"))
    )
    (net (code "63") (name "GND") (class "Default")
      (node (ref "C1") (pin "2") (pinfunction "2_2") (pintype "passive"))
      (node (ref "C10") (pin "2") (pinfunction "2_2") (pintype "passive"))
      (node (ref "C11") (pin "2") (pinfunction "2_2") (pintype "passive"))
      (node (ref "C12") (pin "1") (pinfunction "1_1") (pintype "passive"))
      (node (ref "C13") (pin "1") (pinfunction "1_1") (pintype "passive"))
      (node (ref "C14") (pin "1") (pinfunction "1_1") (pintype "passive"))
      (node (ref "C16") (pin "1") (pinfunction "1_1") (pintype "passive"))
      (node (ref "C17") (pin "1") (pinfunction "1_1") (pintype "passive"))
      (node (ref "C18") (pin "1") (pinfunction "1_1") (pintype "passive"))
      (node (ref "C19") (pin "1") (pinfunction "1_1") (pintype "passive"))
      (node (ref "C2") (pin "2") (pinfunction "2_2") (pintype "passive"))
      (node (ref "C20") (pin "2") (pinfunction "2_2") (pintype "passive"))
      (node (ref "C22") (pin "2") (pinfunction "2_2") (pintype "passive"))
      (node (ref "C23") (pin "1") (pinfunction "1_1") (pintype "passive"))
      (node (ref "C24") (pin "2") (pinfunction "2_2") (pintype "passive"))
      (node (ref "C25") (pin "1") (pinfunction "1_1") (pintype "passive"))
      (node (ref "C26") (pin "1") (pinfunction "1_1") (pintype "passive"))
      (node (ref "C28") (pin "2") (pinfunction "2_2") (pintype "passive"))
      (node (ref "C3") (pin "2") (pinfunction "2_2") (pintype "passive"))
      (node (ref "C4") (pin "2") (pinfunction "2_2") (pintype "passive"))
      (node (ref "C5") (pin "2") (pinfunction "2_2") (pintype "passive"))
      (node (ref "C6") (pin "2") (pinfunction "2_2") (pintype "passive"))
      (node (ref "C7") (pin "1") (pinfunction "1_1") (pintype "passive"))
      (node (ref "C74") (pin "2") (pinfunction "2_2") (pintype "passive"))
      (node (ref "C75") (pin "2") (pinfunction "2_2") (pintype "passive"))
      (node (ref "C8") (pin "1") (pinfunction "1_1") (pintype "passive"))
      (node (ref "C81") (pin "2") (pinfunction "2_2") (pintype "passive"))
      (node (ref "C82") (pin "2") (pinfunction "2_2") (pintype "passive"))
      (node (ref "C84") (pin "2") (pinfunction "2_2") (pintype "passive"))
      (node (ref "C9") (pin "2") (pinfunction "2_2") (pintype "passive"))
      (node (ref "CN1S") (pin "1") (pinfunction "1_1") (pintype "passive"))
      (node (ref "CN1W") (pin "1") (pinfunction "1_1") (pintype "passive"))
      (node (ref "L7") (pin "1") (pinfunction "1_1") (pintype "passive"))
      (node (ref "M1") (pin "A1") (pinfunction "GND_A1") (pintype "passive"))
      (node (ref "M1") (pin "A13") (pinfunction "GND_A13") (pintype "passive"))
      (node (ref "M1") (pin "A14") (pinfunction "GND_A14") (pintype "passive"))
      (node (ref "M1") (pin "A2") (pinfunction "GND_A2") (pintype "passive"))
      (node (ref "Q6") (pin "2") (pinfunction "S_2") (pintype "passive"))
      (node (ref "Q8") (pin "2") (pinfunction "E_2") (pintype "passive"))
      (node (ref "R102") (pin "2") (pinfunction "2_2") (pintype "passive"))
      (node (ref "R105") (pin "1") (pinfunction "1_1") (pintype "passive"))
      (node (ref "R13") (pin "1") (pinfunction "1_1") (pintype "passive"))
      (node (ref "R15") (pin "1") (pinfunction "1_1") (pintype "passive"))
      (node (ref "R18") (pin "1") (pinfunction "1_1") (pintype "passive"))
      (node (ref "R20") (pin "1") (pinfunction "1_1") (pintype "passive"))
      (node (ref "R27") (pin "1") (pinfunction "1_1") (pintype "passive"))
      (node (ref "R3") (pin "1") (pinfunction "1_1") (pintype "passive"))
      (node (ref "R5") (pin "1") (pinfunction "1_1") (pintype "passive"))
      (node (ref "R92") (pin "1") (pinfunction "1_1") (pintype "passive"))
      (node (ref "SW1B") (pin "2") (pinfunction "2_2") (pintype "passive"))
      (node (ref "TP180") (pin "1") (pinfunction "1_1") (pintype "passive"))
      (node (ref "U1") (pin "12") (pinfunction "VSSA_12") (pintype "power_in"))
      (node (ref "U1") (pin "19") (pinfunction "VDD_4_19") (pintype "power_in"))
      (node (ref "U1") (pin "31") (pinfunction "VSS_1_31") (pintype "power_in"))
      (node (ref "U1") (pin "47") (pinfunction "VSS_2_47") (pintype "power_in"))
      (node (ref "U1") (pin "63") (pinfunction "VSS_3_63") (pintype "power_in"))
      (node (ref "U2") (pin "3") (pinfunction "E2_3") (pintype "passive"))
      (node (ref "U2") (pin "4") (pinfunction "Vss_4") (pintype "power_in"))
      (node (ref "U3") (pin "4") (pinfunction "Vss_4") (pintype "power_in"))
      (node (ref "U35") (pin "2") (pinfunction "GND_2") (pintype "passive"))
      (node (ref "U5") (pin "2") (pinfunction "GND_2") (pintype "passive"))
      (node (ref "U6") (pin "2") (pinfunction "GND_2") (pintype "passive"))
      (node (ref "U7") (pin "13") (pinfunction "GND_13") (pintype "power_in"))
      (node (ref "U7") (pin "5") (pinfunction "GND_5") (pintype "power_in"))
      (node (ref "X1") (pin "2") (pinfunction "2_2") (pintype "passive"))
    )
    (net (code "64") (name "Net-(C27-Pad1)") (class "Default")
      (node (ref "C27") (pin "1") (pinfunction "1_1") (pintype "passive"))
      (node (ref "L1") (pin "2") (pinfunction "2_2") (pintype "passive"))
      (node (ref "P1") (pin "1") (pinfunction "1_1") (pintype "passive"))
      (node (ref "TP59") (pin "1") (pinfunction "1_1") (pintype "passive"))
    )
    (net (code "65") (name "Net-(CN2-D+)") (class "Default")
      (node (ref "C25") (pin "2") (pinfunction "2_2") (pintype "passive"))
      (node (ref "CN2") (pin "3") (pinfunction "D+_3") (pintype "passive"))
      (node (ref "R25") (pin "2") (pinfunction "2_2") (pintype "passive"))
      (node (ref "TP61") (pin "1") (pinfunction "1_1") (pintype "passive"))
      (node (ref "V1") (pin "2") (pinfunction "2_2") (pintype "passive"))
    )
    (net (code "66") (name "Net-(CN2-D-)") (class "Default")
      (node (ref "C26") (pin "2") (pinfunction "2_2") (pintype "passive"))
      (node (ref "CN2") (pin "2") (pinfunction "D-_2") (pintype "passive"))
      (node (ref "R24") (pin "2") (pinfunction "2_2") (pintype "passive"))
      (node (ref "TP62") (pin "1") (pinfunction "1_1") (pintype "passive"))
      (node (ref "V2") (pin "2") (pinfunction "2_2") (pintype "passive"))
    )
    (net (code "67") (name "Net-(CN2-GND)") (class "Default")
      (node (ref "C27") (pin "2") (pinfunction "2_2") (pintype "passive"))
      (node (ref "CN2") (pin "5") (pinfunction "GND_5") (pintype "passive"))
      (node (ref "L7") (pin "2") (pinfunction "2_2") (pintype "passive"))
      (node (ref "R92") (pin "2") (pinfunction "2_2") (pintype "passive"))
      (node (ref "TP75") (pin "1") (pinfunction "1_1") (pintype "passive"))
      (node (ref "V1") (pin "1") (pinfunction "1_1") (pintype "passive"))
      (node (ref "V2") (pin "1") (pinfunction "1_1") (pintype "passive"))
      (node (ref "V3") (pin "1") (pinfunction "1_1") (pintype "passive"))
    )
    (net (code "68") (name "Net-(CN2-VCC)") (class "Default")
      (node (ref "CN2") (pin "1") (pinfunction "VCC_1") (pintype "passive"))
      (node (ref "P1") (pin "2") (pinfunction "2_2") (pintype "passive"))
      (node (ref "TP58") (pin "1") (pinfunction "1_1") (pintype "passive"))
      (node (ref "V3") (pin "2") (pinfunction "2_2") (pintype "passive"))
    )
    (net (code "69") (name "Net-(D1-K)") (class "Default")
      (node (ref "C11") (pin "1") (pinfunction "1_1") (pintype "passive"))
      (node (ref "D1") (pin "1") (pinfunction "K_1") (pintype "passive"))
      (node (ref "R2") (pin "2") (pinfunction "2_2") (pintype "passive"))
      (node (ref "TP45") (pin "1") (pinfunction "1_1") (pintype "passive"))
    )
    (net (code "70") (name "Net-(M1-3V3-PadC14)") (class "Default")
      (node (ref "M1") (pin "C14") (pinfunction "3V3_C14") (pintype "passive"))
      (node (ref "M1") (pin "C15") (pinfunction "3V3_C15") (pintype "passive"))
      (node (ref "M1") (pin "C16") (pinfunction "3V3_C16") (pintype "passive"))
      (node (ref "R104") (pin "2") (pinfunction "2_2") (pintype "passive"))
      (node (ref "R106") (pin "1") (pinfunction "1_1") (pintype "passive"))
      (node (ref "TP190") (pin "1") (pinfunction "1_1") (pintype "passive"))
    )
    (net (code "71") (name "Net-(M1-CC_IO14_SCLK)") (class "Default")
      (node (ref "M1") (pin "A5") (pinfunction "CC_IO14_SCLK_A5") (pintype "passive"))
      (node (ref "R83") (pin "1") (pinfunction "1_1") (pintype "passive"))
      (node (ref "TP102") (pin "1") (pinfunction "1_1") (pintype "passive"))
    )
    (net (code "72") (name "Net-(M1-CC_IO15_SMISO)") (class "Default")
      (node (ref "M1") (pin "A6") (pinfunction "CC_IO15_SMISO_A6") (pintype "passive"))
      (node (ref "R82") (pin "1") (pinfunction "1_1") (pintype "passive"))
      (node (ref "TP103") (pin "1") (pinfunction "1_1") (pintype "passive"))
    )
    (net (code "73") (name "Net-(M1-CC_IO16_UTX_SMOSI)") (class "Default")
      (node (ref "M1") (pin "A7") (pinfunction "CC_IO16_UTX_SMOSI_A7") (pintype "passive"))
      (node (ref "R80") (pin "1") (pinfunction "1_1") (pintype "passive"))
      (node (ref "R81") (pin "1") (pinfunction "1_1") (pintype "passive"))
      (node (ref "TP104") (pin "1") (pinfunction "1_1") (pintype "passive"))
    )
    (net (code "74") (name "Net-(M1-CC_IO17_URX_SCS)") (class "Default")
      (node (ref "M1") (pin "A8") (pinfunction "CC_IO17_URX_SCS_A8") (pintype "passive"))
      (node (ref "R78") (pin "1") (pinfunction "1_1") (pintype "passive"))
      (node (ref "R79") (pin "1") (pinfunction "1_1") (pintype "passive"))
      (node (ref "TP105") (pin "1") (pinfunction "1_1") (pintype "passive"))
    )
    (net (code "75") (name "Net-(Q1-G)") (class "Default")
      (node (ref "C21") (pin "1") (pinfunction "1_1") (pintype "passive"))
      (node (ref "Q1") (pin "1") (pinfunction "G_1") (pintype "passive"))
      (node (ref "R22") (pin "2") (pinfunction "2_2") (pintype "passive"))
      (node (ref "R23") (pin "2") (pinfunction "2_2") (pintype "passive"))
      (node (ref "TP66") (pin "1") (pinfunction "1_1") (pintype "passive"))
    )
    (net (code "76") (name "Net-(Q1-S)") (class "Default")
      (node (ref "C22") (pin "1") (pinfunction "1_1") (pintype "passive"))
      (node (ref "C28") (pin "1") (pinfunction "1_1") (pintype "passive"))
      (node (ref "L1") (pin "1") (pinfunction "1_1") (pintype "passive"))
      (node (ref "Q1") (pin "2") (pinfunction "S_2") (pintype "passive"))
      (node (ref "R22") (pin "1") (pinfunction "1_1") (pintype "passive"))
      (node (ref "R26") (pin "2") (pinfunction "2_2") (pintype "passive"))
      (node (ref "TP60") (pin "1") (pinfunction "1_1") (pintype "passive"))
      (node (ref "U7") (pin "12") (pinfunction "VCC_12") (pintype "power_in"))
    )
    (net (code "77") (name "Net-(Q6-D)") (class "Default")
      (node (ref "C79") (pin "2") (pinfunction "2_2") (pintype "passive"))
      (node (ref "Q6") (pin "3") (pinfunction "D_3") (pintype "passive"))
      (node (ref "Q7") (pin "1") (pinfunction "G_1") (pintype "passive"))
      (node (ref "R21") (pin "2") (pinfunction "2_2") (pintype "passive"))
      (node (ref "TP181") (pin "1") (pinfunction "1_1") (pintype "passive"))
    )
    (net (code "78") (name "Net-(Q8-B)") (class "Default")
      (node (ref "Q8") (pin "1") (pinfunction "B_1") (pintype "passive"))
      (node (ref "R101") (pin "2") (pinfunction "2_2") (pintype "passive"))
    )
    (net (code "79") (name "Net-(Q8-C)") (class "Default")
      (node (ref "Q8") (pin "3") (pinfunction "C_3") (pintype "passive"))
      (node (ref "R100") (pin "1") (pinfunction "1_1") (pintype "passive"))
      (node (ref "TP188") (pin "1") (pinfunction "1_1") (pintype "passive"))
      (node (ref "U35") (pin "3") (pinfunction "EN_3") (pintype "passive"))
    )
    (net (code "80") (name "Net-(R11-Pad1)") (class "Default")
      (node (ref "R11") (pin "1") (pinfunction "1_1") (pintype "passive"))
      (node (ref "R12") (pin "2") (pinfunction "2_2") (pintype "passive"))
      (node (ref "TP73") (pin "1") (pinfunction "1_1") (pintype "passive"))
    )
    (net (code "81") (name "Net-(R16-Pad1)") (class "Default")
      (node (ref "R16") (pin "1") (pinfunction "1_1") (pintype "passive"))
      (node (ref "R17") (pin "2") (pinfunction "2_2") (pintype "passive"))
      (node (ref "TP69") (pin "1") (pinfunction "1_1") (pintype "passive"))
    )
    (net (code "82") (name "Net-(U1-PC8)") (class "Default")
      (node (ref "R103") (pin "2") (pinfunction "2_2") (pintype "passive"))
      (node (ref "TP87") (pin "1") (pinfunction "1_1") (pintype "passive"))
      (node (ref "U1") (pin "39") (pinfunction "PC8_39") (pintype "bidirectional"))
    )
    (net (code "83") (name "Net-(U1-PC14-OSC32_IN)") (class "Default")
      (node (ref "C6") (pin "1") (pinfunction "1_1") (pintype "passive"))
      (node (ref "U1") (pin "3") (pinfunction "PC14-OSC32_IN_3") (pintype "bidirectional"))
      (node (ref "X3") (pin "1") (pinfunction "1_1") (pintype "passive"))
    )
    (net (code "84") (name "Net-(U1-PC15-OSC32_OUT)") (class "Default")
      (node (ref "C7") (pin "2") (pinfunction "2_2") (pintype "passive"))
      (node (ref "U1") (pin "4") (pinfunction "PC15-OSC32_OUT_4") (pintype "bidirectional"))
      (node (ref "X3") (pin "4") (pinfunction "4_4") (pintype "passive"))
    )
    (net (code "85") (name "Net-(U1-PD0-OSC_IN)") (class "Default")
      (node (ref "U1") (pin "5") (pinfunction "PD0-OSC_IN_5") (pintype "bidirectional"))
      (node (ref "X1") (pin "1") (pinfunction "1_1") (pintype "passive"))
    )
    (net (code "86") (name "Net-(U1-PD1-OSC_OUT)") (class "Default")
      (node (ref "U1") (pin "6") (pinfunction "PD1-OSC_OUT_6") (pintype "bidirectional"))
      (node (ref "X1") (pin "3") (pinfunction "3_3") (pintype "passive"))
    )
    (net (code "87") (name "Net-(U1-VBAT)") (class "Default")
      (node (ref "R1") (pin "2") (pinfunction "2_2") (pintype "passive"))
      (node (ref "R2") (pin "1") (pinfunction "1_1") (pintype "passive"))
      (node (ref "TP47") (pin "1") (pinfunction "1_1") (pintype "passive"))
      (node (ref "U1") (pin "1") (pinfunction "VBAT_1") (pintype "power_in"))
    )
    (net (code "88") (name "Net-(U5-ADJ)") (class "Default")
      (node (ref "C74") (pin "1") (pinfunction "1_1") (pintype "passive"))
      (node (ref "R12") (pin "1") (pinfunction "1_1") (pintype "passive"))
      (node (ref "R13") (pin "2") (pinfunction "2_2") (pintype "passive"))
      (node (ref "TP72") (pin "1") (pinfunction "1_1") (pintype "passive"))
      (node (ref "U5") (pin "4") (pinfunction "ADJ_4") (pintype "passive"))
    )
    (net (code "89") (name "Net-(U5-EN)") (class "Default")
      (node (ref "R99") (pin "2") (pinfunction "2_2") (pintype "passive"))
      (node (ref "TP183") (pin "1") (pinfunction "1_1") (pintype "passive"))
      (node (ref "U5") (pin "3") (pinfunction "EN_3") (pintype "passive"))
    )
    (net (code "90") (name "Net-(U6-ADJ)") (class "Default")
      (node (ref "C75") (pin "1") (pinfunction "1_1") (pintype "passive"))
      (node (ref "R17") (pin "1") (pinfunction "1_1") (pintype "passive"))
      (node (ref "R18") (pin "2") (pinfunction "2_2") (pintype "passive"))
      (node (ref "TP68") (pin "1") (pinfunction "1_1") (pintype "passive"))
      (node (ref "U6") (pin "4") (pinfunction "ADJ_4") (pintype "passive"))
    )
    (net (code "91") (name "Net-(U6-EN)") (class "Default")
      (node (ref "R19") (pin "2") (pinfunction "2_2") (pintype "passive"))
      (node (ref "TP182") (pin "1") (pinfunction "1_1") (pintype "passive"))
      (node (ref "U6") (pin "3") (pinfunction "EN_3") (pintype "passive"))
    )
    (net (code "92") (name "Net-(U7-3V3OUT)") (class "Default")
      (node (ref "C23") (pin "2") (pinfunction "2_2") (pintype "passive"))
      (node (ref "R88") (pin "1") (pinfunction "1_1") (pintype "passive"))
      (node (ref "TP56") (pin "1") (pinfunction "1_1") (pintype "passive"))
      (node (ref "U7") (pin "10") (pinfunction "3V3OUT_10") (pintype "power_in"))
      (node (ref "U7") (pin "3") (pinfunction "VCCIO_3") (pintype "power_in"))
    )
    (net (code "93") (name "Net-(U7-RESET#)") (class "Default")
      (node (ref "C24") (pin "1") (pinfunction "1_1") (pintype "passive"))
      (node (ref "R26") (pin "1") (pinfunction "1_1") (pintype "passive"))
      (node (ref "R27") (pin "2") (pinfunction "2_2") (pintype "passive"))
      (node (ref "R88") (pin "2") (pinfunction "2_2") (pintype "passive"))
      (node (ref "TP57") (pin "1") (pinfunction "1_1") (pintype "passive"))
      (node (ref "U7") (pin "11") (pinfunction "RESET#_11") (pintype "passive"))
    )
    (net (code "94") (name "Net-(U7-USBDM)") (class "Default")
      (node (ref "R24") (pin "1") (pinfunction "1_1") (pintype "passive"))
      (node (ref "TP64") (pin "1") (pinfunction "1_1") (pintype "passive"))
      (node (ref "U7") (pin "9") (pinfunction "USBDM_9") (pintype "passive"))
    )
    (net (code "95") (name "Net-(U7-USBDP)") (class "Default")
      (node (ref "R25") (pin "1") (pinfunction "1_1") (pintype "passive"))
      (node (ref "TP63") (pin "1") (pinfunction "1_1") (pintype "passive"))
      (node (ref "U7") (pin "8") (pinfunction "USBDP_8") (pintype "passive"))
    )
    (net (code "96") (name "Net-(U35-BYP)") (class "Default")
      (node (ref "C84") (pin "1") (pinfunction "1_1") (pintype "passive"))
      (node (ref "TP193") (pin "1") (pinfunction "1_1") (pintype "passive"))
      (node (ref "U35") (pin "4") (pinfunction "BYP_4") (pintype "passive"))
    )
    (net (code "97") (name "unconnected-(CN2-ID-Pad4)") (class "Default")
      (node (ref "CN2") (pin "4") (pinfunction "ID_4") (pintype "passive"))
    )
    (net (code "98") (name "unconnected-(U1-PB5-Pad57)") (class "Default")
      (node (ref "U1") (pin "57") (pinfunction "PB5_57") (pintype "bidirectional"))
    )
    (net (code "99") (name "unconnected-(U2-DU-Pad1)") (class "Default")
      (node (ref "U2") (pin "1") (pinfunction "DU_1") (pintype "passive"))
    )
    (net (code "100") (name "unconnected-(U2-DU-Pad2)") (class "Default")
      (node (ref "U2") (pin "2") (pinfunction "DU_2") (pintype "passive"))
    )
    (net (code "101") (name "unconnected-(U3-DU-Pad1)") (class "Default")
      (node (ref "U3") (pin "1") (pinfunction "DU_1") (pintype "passive"))
    )
    (net (code "102") (name "unconnected-(U3-DU-Pad2)") (class "Default")
      (node (ref "U3") (pin "2") (pinfunction "DU_2") (pintype "passive"))
    )
    (net (code "103") (name "unconnected-(U7-CBUS0-Pad15)") (class "Default")
      (node (ref "U7") (pin "15") (pinfunction "CBUS0_15") (pintype "passive"))
    )
    (net (code "104") (name "unconnected-(U7-CBUS1-Pad14)") (class "Default")
      (node (ref "U7") (pin "14") (pinfunction "CBUS1_14") (pintype "passive"))
    )
    (net (code "105") (name "unconnected-(U7-CBUS2-Pad7)") (class "Default")
      (node (ref "U7") (pin "7") (pinfunction "CBUS2_7") (pintype "passive"))
    )
    (net (code "106") (name "unconnected-(U7-CTS#-Pad6)") (class "Default")
      (node (ref "U7") (pin "6") (pinfunction "CTS#_6") (pintype "passive"))
    )
    (net (code "107") (name "unconnected-(U7-RTS#-Pad2)") (class "Default")
      (node (ref "U7") (pin "2") (pinfunction "RTS#_2") (pintype "passive"))
    )
    (net (code "108") (name "unconnected-(X3-Pad2)") (class "Default")
      (node (ref "X3") (pin "2") (pinfunction "2_2") (pintype "passive"))
    )
    (net (code "109") (name "unconnected-(X3-Pad3)") (class "Default")
      (node (ref "X3") (pin "3") (pinfunction "3_3") (pintype "passive"))
    )
  )
)
